# RAMBo.net
KiCad netlist of a schematic drawn in EAGLE
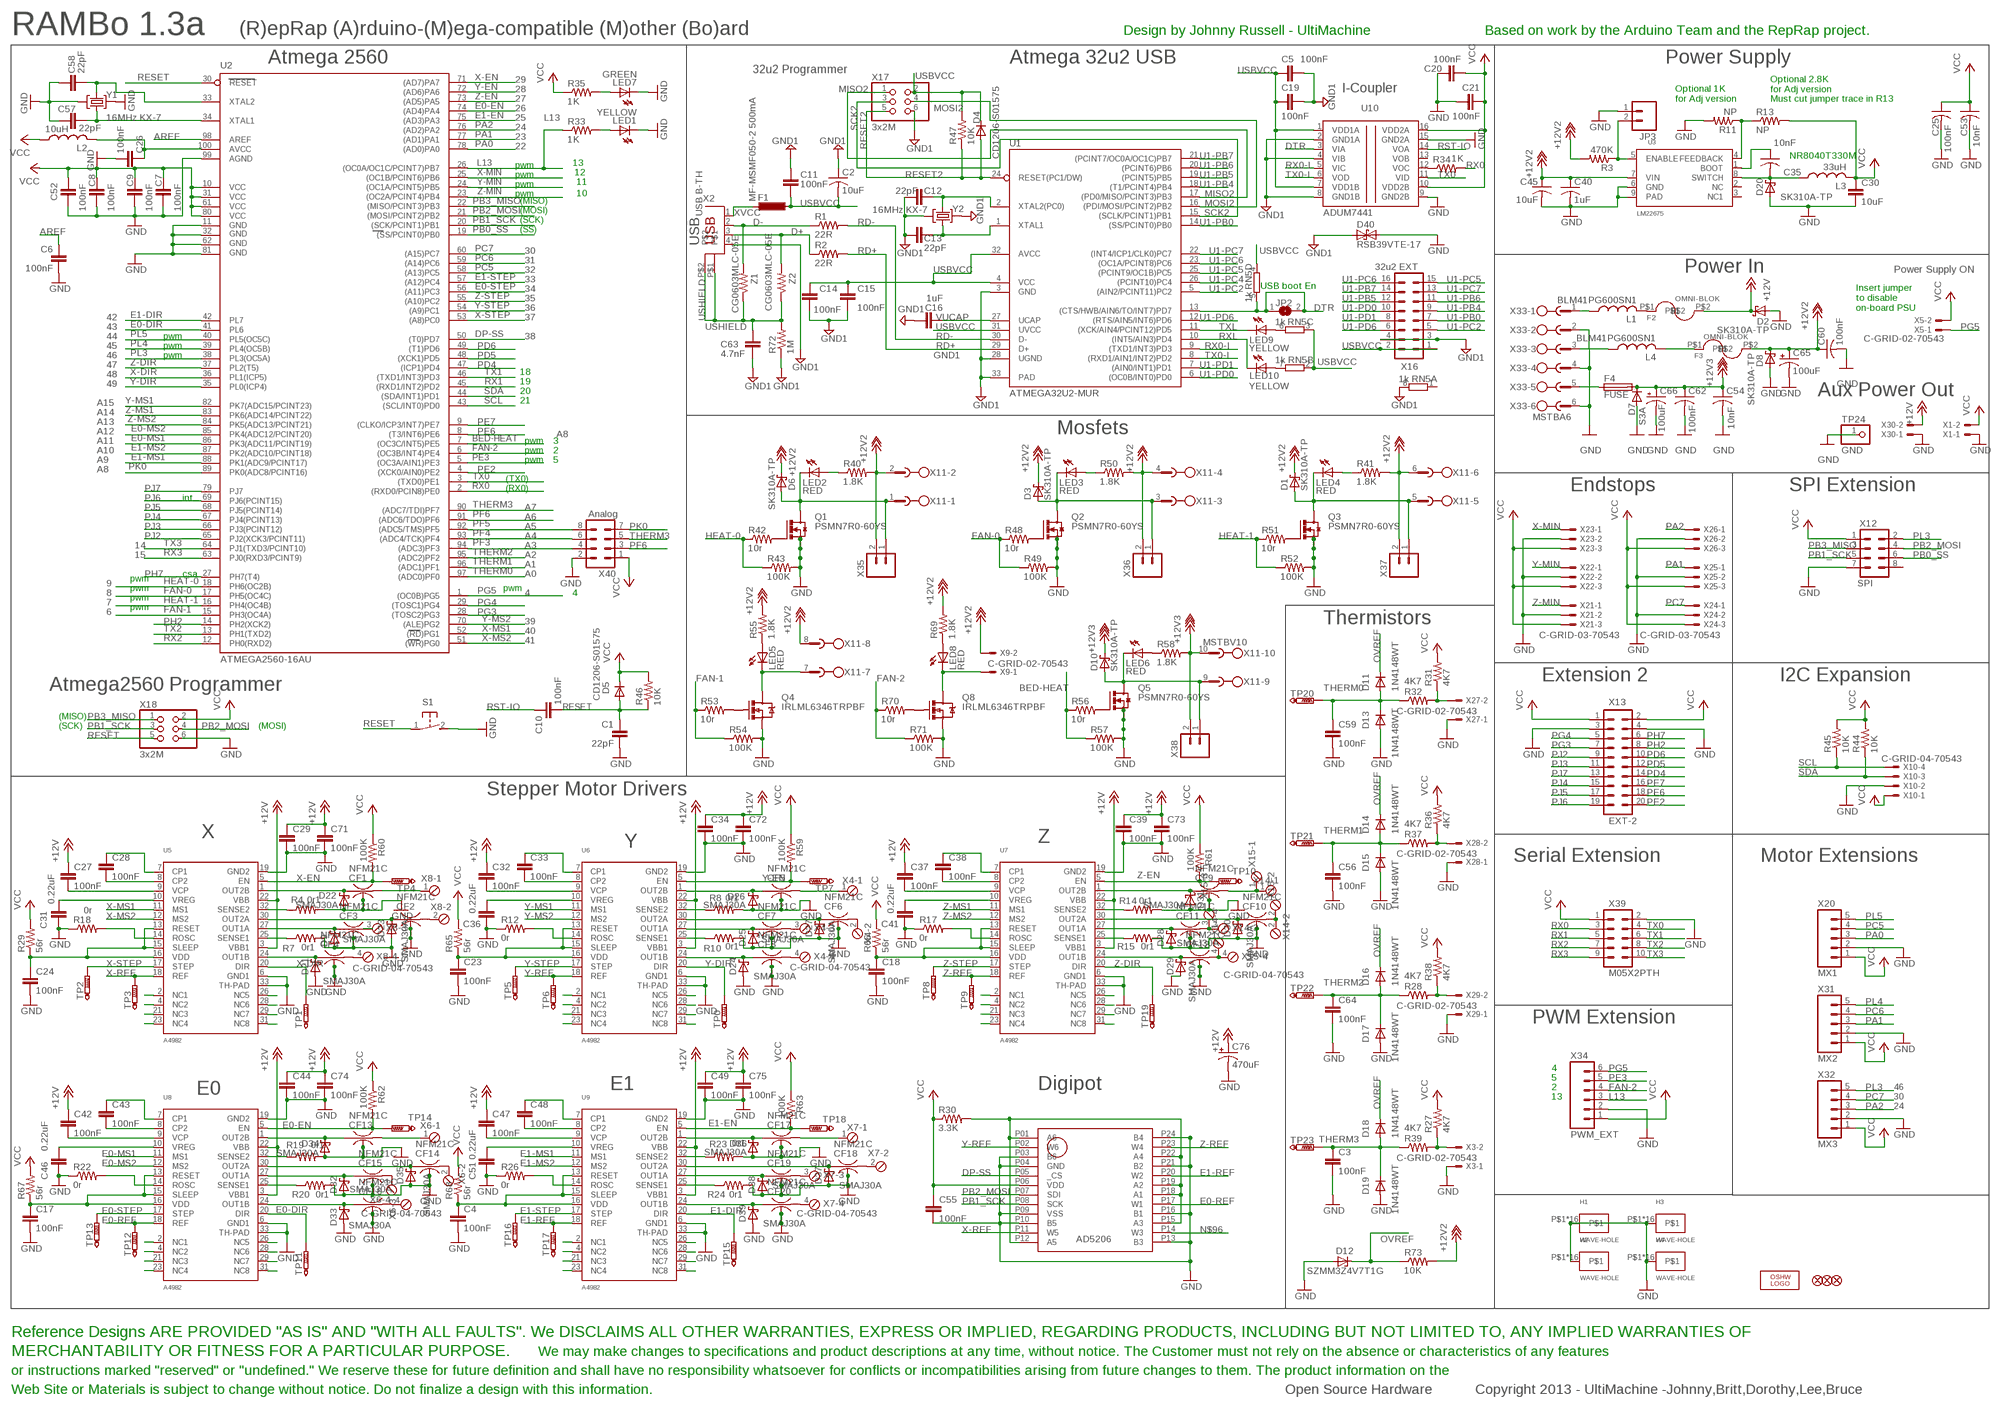
[diagram p0: schematic, sheet 1]

(export (version "E")
  (design (tool "Eeschema 10.0.6"))
  (components
    (comp (ref "C1")
      (value "22pF")
      (footprint "eagle-import:C0603")
      (libsource (lib "eagle-import") (part "resistor_C-EUC0603"))
    )
    (comp (ref "C2")
      (value "10uF")
      (footprint "eagle-import:C0805")
      (libsource (lib "eagle-import") (part "C-USC0805"))
    )
    (comp (ref "C3")
      (value "100nF")
      (footprint "eagle-import:C0603")
      (libsource (lib "eagle-import") (part "resistor_C-EUC0603"))
    )
    (comp (ref "C4")
      (value "100nF")
      (footprint "eagle-import:C0603")
      (libsource (lib "eagle-import") (part "resistor_C-EUC0603"))
    )
    (comp (ref "C5")
      (value "100nF")
      (footprint "eagle-import:C0402")
      (libsource (lib "eagle-import") (part "C-EUC0402"))
    )
    (comp (ref "C6")
      (value "100nF")
      (footprint "eagle-import:C0603")
      (libsource (lib "eagle-import") (part "resistor_C-EUC0603"))
    )
    (comp (ref "C7")
      (value "100nF")
      (footprint "eagle-import:C0603")
      (libsource (lib "eagle-import") (part "resistor_C-EUC0603"))
    )
    (comp (ref "C8")
      (value "100nF")
      (footprint "eagle-import:C0603")
      (libsource (lib "eagle-import") (part "resistor_C-EUC0603"))
    )
    (comp (ref "C9")
      (value "100nF")
      (footprint "eagle-import:C0603")
      (libsource (lib "eagle-import") (part "resistor_C-EUC0603"))
    )
    (comp (ref "C10")
      (value "100nF")
      (footprint "eagle-import:C0603")
      (libsource (lib "eagle-import") (part "resistor_C-EUC0603"))
    )
    (comp (ref "C11")
      (value "100nF")
      (footprint "eagle-import:C0603")
      (libsource (lib "eagle-import") (part "resistor_C-EUC0603"))
    )
    (comp (ref "C12")
      (value "22pF")
      (footprint "eagle-import:C0603")
      (libsource (lib "eagle-import") (part "resistor_C-EUC0603"))
    )
    (comp (ref "C13")
      (value "22pF")
      (footprint "eagle-import:C0603")
      (libsource (lib "eagle-import") (part "resistor_C-EUC0603"))
    )
    (comp (ref "C14")
      (value "100nF")
      (footprint "eagle-import:C0603")
      (libsource (lib "eagle-import") (part "resistor_C-EUC0603"))
    )
    (comp (ref "C15")
      (value "100nF")
      (footprint "eagle-import:C0603")
      (libsource (lib "eagle-import") (part "resistor_C-EUC0603"))
    )
    (comp (ref "C16")
      (value "1uF")
      (footprint "eagle-import:C0603")
      (libsource (lib "eagle-import") (part "resistor_C-EUC0603"))
    )
    (comp (ref "C17")
      (value "100nF")
      (footprint "eagle-import:C0603")
      (libsource (lib "eagle-import") (part "resistor_C-EUC0603"))
    )
    (comp (ref "C18")
      (value "100nF")
      (footprint "eagle-import:C0603")
      (libsource (lib "eagle-import") (part "resistor_C-EUC0603"))
    )
    (comp (ref "C19")
      (value "100nF")
      (footprint "eagle-import:C0402")
      (libsource (lib "eagle-import") (part "C-EUC0402"))
    )
    (comp (ref "C20")
      (value "100nF")
      (footprint "eagle-import:C0402")
      (libsource (lib "eagle-import") (part "C-EUC0402"))
    )
    (comp (ref "C21")
      (value "100nF")
      (footprint "eagle-import:C0402")
      (libsource (lib "eagle-import") (part "C-EUC0402"))
    )
    (comp (ref "C23")
      (value "100nF")
      (footprint "eagle-import:C0603")
      (libsource (lib "eagle-import") (part "resistor_C-EUC0603"))
    )
    (comp (ref "C24")
      (value "100nF")
      (footprint "eagle-import:C0603")
      (libsource (lib "eagle-import") (part "resistor_C-EUC0603"))
    )
    (comp (ref "C25")
      (value "100nF")
      (footprint "eagle-import:C0603")
      (libsource (lib "eagle-import") (part "C-USC0603"))
    )
    (comp (ref "C26")
      (value "100nF")
      (footprint "eagle-import:C0603")
      (libsource (lib "eagle-import") (part "resistor_C-EUC0603"))
    )
    (comp (ref "C27")
      (value "100nF")
      (footprint "eagle-import:C0603")
      (libsource (lib "eagle-import") (part "resistor_C-EUC0603"))
    )
    (comp (ref "C28")
      (value "100nF")
      (footprint "eagle-import:C0603")
      (libsource (lib "eagle-import") (part "resistor_C-EUC0603"))
    )
    (comp (ref "C29")
      (value "100nF")
      (footprint "eagle-import:C0603")
      (libsource (lib "eagle-import") (part "resistor_C-EUC0603"))
    )
    (comp (ref "C30")
      (value "10uF")
      (footprint "eagle-import:C1210K")
      (libsource (lib "eagle-import") (part "resistor_C-EUC1210K"))
    )
    (comp (ref "C31")
      (value "0.22uF")
      (footprint "eagle-import:C0603")
      (libsource (lib "eagle-import") (part "resistor_C-EUC0603"))
    )
    (comp (ref "C32")
      (value "100nF")
      (footprint "eagle-import:C0603")
      (libsource (lib "eagle-import") (part "resistor_C-EUC0603"))
    )
    (comp (ref "C33")
      (value "100nF")
      (footprint "eagle-import:C0603")
      (libsource (lib "eagle-import") (part "resistor_C-EUC0603"))
    )
    (comp (ref "C34")
      (value "100nF")
      (footprint "eagle-import:C0603")
      (libsource (lib "eagle-import") (part "resistor_C-EUC0603"))
    )
    (comp (ref "C35")
      (value "10nF")
      (footprint "eagle-import:C0603")
      (libsource (lib "eagle-import") (part "C-USC0603"))
    )
    (comp (ref "C36")
      (value "0.22uF")
      (footprint "eagle-import:C0603")
      (libsource (lib "eagle-import") (part "resistor_C-EUC0603"))
    )
    (comp (ref "C37")
      (value "100nF")
      (footprint "eagle-import:C0603")
      (libsource (lib "eagle-import") (part "resistor_C-EUC0603"))
    )
    (comp (ref "C38")
      (value "100nF")
      (footprint "eagle-import:C0603")
      (libsource (lib "eagle-import") (part "resistor_C-EUC0603"))
    )
    (comp (ref "C39")
      (value "100nF")
      (footprint "eagle-import:C0603")
      (libsource (lib "eagle-import") (part "resistor_C-EUC0603"))
    )
    (comp (ref "C40")
      (value "1uF")
      (footprint "eagle-import:C0805")
      (libsource (lib "eagle-import") (part "C-USC0805"))
    )
    (comp (ref "C41")
      (value "0.22uF")
      (footprint "eagle-import:C0603")
      (libsource (lib "eagle-import") (part "resistor_C-EUC0603"))
    )
    (comp (ref "C42")
      (value "100nF")
      (footprint "eagle-import:C0603")
      (libsource (lib "eagle-import") (part "resistor_C-EUC0603"))
    )
    (comp (ref "C43")
      (value "100nF")
      (footprint "eagle-import:C0603")
      (libsource (lib "eagle-import") (part "resistor_C-EUC0603"))
    )
    (comp (ref "C44")
      (value "100nF")
      (footprint "eagle-import:C0603")
      (libsource (lib "eagle-import") (part "resistor_C-EUC0603"))
    )
    (comp (ref "C45")
      (value "10uF")
      (footprint "eagle-import:C2220K")
      (libsource (lib "eagle-import") (part "C-USC2220K"))
    )
    (comp (ref "C46")
      (value "0.22uF")
      (footprint "eagle-import:C0603")
      (libsource (lib "eagle-import") (part "resistor_C-EUC0603"))
    )
    (comp (ref "C47")
      (value "100nF")
      (footprint "eagle-import:C0603")
      (libsource (lib "eagle-import") (part "resistor_C-EUC0603"))
    )
    (comp (ref "C48")
      (value "100nF")
      (footprint "eagle-import:C0603")
      (libsource (lib "eagle-import") (part "resistor_C-EUC0603"))
    )
    (comp (ref "C49")
      (value "100nF")
      (footprint "eagle-import:C0603")
      (libsource (lib "eagle-import") (part "resistor_C-EUC0603"))
    )
    (comp (ref "C51")
      (value "0.22uF")
      (footprint "eagle-import:C0603")
      (libsource (lib "eagle-import") (part "resistor_C-EUC0603"))
    )
    (comp (ref "C52")
      (value "100nF")
      (footprint "eagle-import:C0603")
      (libsource (lib "eagle-import") (part "resistor_C-EUC0603"))
    )
    (comp (ref "C53")
      (value "10nF")
      (footprint "eagle-import:C0603")
      (libsource (lib "eagle-import") (part "C-USC0603"))
    )
    (comp (ref "C54")
      (value "10nF")
      (footprint "eagle-import:C0603")
      (libsource (lib "eagle-import") (part "C-USC0603"))
    )
    (comp (ref "C55")
      (value "100nF")
      (footprint "eagle-import:C0603")
      (libsource (lib "eagle-import") (part "resistor_C-EUC0603"))
    )
    (comp (ref "C56")
      (value "100nF")
      (footprint "eagle-import:C0603")
      (libsource (lib "eagle-import") (part "resistor_C-EUC0603"))
    )
    (comp (ref "C57")
      (value "22pF")
      (footprint "eagle-import:C0603")
      (libsource (lib "eagle-import") (part "resistor_C-EUC0603"))
    )
    (comp (ref "C58")
      (value "22pF")
      (footprint "eagle-import:C0603")
      (libsource (lib "eagle-import") (part "resistor_C-EUC0603"))
    )
    (comp (ref "C59")
      (value "100nF")
      (footprint "eagle-import:C0603")
      (libsource (lib "eagle-import") (part "resistor_C-EUC0603"))
    )
    (comp (ref "C60")
      (value "100nF")
      (footprint "eagle-import:C0603")
      (libsource (lib "eagle-import") (part "C-USC0603"))
    )
    (comp (ref "C62")
      (value "100nF")
      (footprint "eagle-import:C0603")
      (libsource (lib "eagle-import") (part "C-USC0603"))
    )
    (comp (ref "C63")
      (value "4.7nF")
      (footprint "eagle-import:C0402")
      (libsource (lib "eagle-import") (part "C-EUC0402"))
    )
    (comp (ref "C64")
      (value "100nF")
      (footprint "eagle-import:C0603")
      (libsource (lib "eagle-import") (part "resistor_C-EUC0603"))
    )
    (comp (ref "C65")
      (value "100uF")
      (footprint "eagle-import:E3,5-8")
      (libsource (lib "eagle-import") (part "CPOL-USE3.5-8"))
    )
    (comp (ref "C66")
      (value "100uF")
      (footprint "eagle-import:E3,5-8")
      (libsource (lib "eagle-import") (part "CPOL-USE3.5-8"))
    )
    (comp (ref "C71")
      (value "100nF")
      (footprint "eagle-import:C0603")
      (libsource (lib "eagle-import") (part "resistor_C-EUC0603"))
    )
    (comp (ref "C72")
      (value "100nF")
      (footprint "eagle-import:C0603")
      (libsource (lib "eagle-import") (part "resistor_C-EUC0603"))
    )
    (comp (ref "C73")
      (value "100nF")
      (footprint "eagle-import:C0603")
      (libsource (lib "eagle-import") (part "resistor_C-EUC0603"))
    )
    (comp (ref "C74")
      (value "100nF")
      (footprint "eagle-import:C0603")
      (libsource (lib "eagle-import") (part "resistor_C-EUC0603"))
    )
    (comp (ref "C75")
      (value "100nF")
      (footprint "eagle-import:C0603")
      (libsource (lib "eagle-import") (part "resistor_C-EUC0603"))
    )
    (comp (ref "C76")
      (value "470uF")
      (footprint "eagle-import:C12,5-5")
      (libsource (lib "eagle-import") (part "CPOL-USC12,5-5"))
    )
    (comp (ref "CF1")
      (value "NFM21C")
      (footprint "eagle-import:NFM21C")
      (fields (field (name "MPN") "NFM21CC102R1H3D"))
      (libsource (lib "eagle-import") (part "NFM21C"))
    )
    (comp (ref "CF2")
      (value "NFM21C")
      (footprint "eagle-import:NFM21C")
      (fields (field (name "MPN") "NFM21CC102R1H3D"))
      (libsource (lib "eagle-import") (part "NFM21C"))
    )
    (comp (ref "CF3")
      (value "NFM21C")
      (footprint "eagle-import:NFM21C")
      (fields (field (name "MPN") "NFM21CC102R1H3D"))
      (libsource (lib "eagle-import") (part "NFM21C"))
    )
    (comp (ref "CF4")
      (value "NFM21C")
      (footprint "eagle-import:NFM21C")
      (fields (field (name "MPN") "NFM21CC102R1H3D"))
      (libsource (lib "eagle-import") (part "NFM21C"))
    )
    (comp (ref "CF5")
      (value "NFM21C")
      (footprint "eagle-import:NFM21C")
      (fields (field (name "MPN") "NFM21CC102R1H3D"))
      (libsource (lib "eagle-import") (part "NFM21C"))
    )
    (comp (ref "CF6")
      (value "NFM21C")
      (footprint "eagle-import:NFM21C")
      (fields (field (name "MPN") "NFM21CC102R1H3D"))
      (libsource (lib "eagle-import") (part "NFM21C"))
    )
    (comp (ref "CF7")
      (value "NFM21C")
      (footprint "eagle-import:NFM21C")
      (fields (field (name "MPN") "NFM21CC102R1H3D"))
      (libsource (lib "eagle-import") (part "NFM21C"))
    )
    (comp (ref "CF8")
      (value "NFM21C")
      (footprint "eagle-import:NFM21C")
      (fields (field (name "MPN") "NFM21CC102R1H3D"))
      (libsource (lib "eagle-import") (part "NFM21C"))
    )
    (comp (ref "CF9")
      (value "NFM21C")
      (footprint "eagle-import:NFM21C")
      (fields (field (name "MPN") "NFM21CC102R1H3D"))
      (libsource (lib "eagle-import") (part "NFM21C"))
    )
    (comp (ref "CF10")
      (value "NFM21C")
      (footprint "eagle-import:NFM21C")
      (fields (field (name "MPN") "NFM21CC102R1H3D"))
      (libsource (lib "eagle-import") (part "NFM21C"))
    )
    (comp (ref "CF11")
      (value "NFM21C")
      (footprint "eagle-import:NFM21C")
      (fields (field (name "MPN") "NFM21CC102R1H3D"))
      (libsource (lib "eagle-import") (part "NFM21C"))
    )
    (comp (ref "CF12")
      (value "NFM21C")
      (footprint "eagle-import:NFM21C")
      (fields (field (name "MPN") "NFM21CC102R1H3D"))
      (libsource (lib "eagle-import") (part "NFM21C"))
    )
    (comp (ref "CF13")
      (value "NFM21C")
      (footprint "eagle-import:NFM21C")
      (fields (field (name "MPN") "NFM21CC102R1H3D"))
      (libsource (lib "eagle-import") (part "NFM21C"))
    )
    (comp (ref "CF14")
      (value "NFM21C")
      (footprint "eagle-import:NFM21C")
      (fields (field (name "MPN") "NFM21CC102R1H3D"))
      (libsource (lib "eagle-import") (part "NFM21C"))
    )
    (comp (ref "CF15")
      (value "NFM21C")
      (footprint "eagle-import:NFM21C")
      (fields (field (name "MPN") "NFM21CC102R1H3D"))
      (libsource (lib "eagle-import") (part "NFM21C"))
    )
    (comp (ref "CF16")
      (value "NFM21C")
      (footprint "eagle-import:NFM21C")
      (fields (field (name "MPN") "NFM21CC102R1H3D"))
      (libsource (lib "eagle-import") (part "NFM21C"))
    )
    (comp (ref "CF17")
      (value "NFM21C")
      (footprint "eagle-import:NFM21C")
      (fields (field (name "MPN") "NFM21CC102R1H3D"))
      (libsource (lib "eagle-import") (part "NFM21C"))
    )
    (comp (ref "CF18")
      (value "NFM21C")
      (footprint "eagle-import:NFM21C")
      (fields (field (name "MPN") "NFM21CC102R1H3D"))
      (libsource (lib "eagle-import") (part "NFM21C"))
    )
    (comp (ref "CF19")
      (value "NFM21C")
      (footprint "eagle-import:NFM21C")
      (fields (field (name "MPN") "NFM21CC102R1H3D"))
      (libsource (lib "eagle-import") (part "NFM21C"))
    )
    (comp (ref "CF20")
      (value "NFM21C")
      (footprint "eagle-import:NFM21C")
      (fields (field (name "MPN") "NFM21CC102R1H3D"))
      (libsource (lib "eagle-import") (part "NFM21C"))
    )
    (comp (ref "D1")
      (value "SK310A-TP")
      (footprint "eagle-import:SMA-SM")
      (libsource (lib "eagle-import") (part "SCHOTTKY-DIODE"))
    )
    (comp (ref "D2")
      (value "SK310A-TP")
      (footprint "eagle-import:SMA-SM")
      (libsource (lib "eagle-import") (part "SCHOTTKY-DIODE"))
    )
    (comp (ref "D3")
      (value "SK310A-TP")
      (footprint "eagle-import:SMA-SM")
      (libsource (lib "eagle-import") (part "SCHOTTKY-DIODE"))
    )
    (comp (ref "D4")
      (value "CD1206-S01575")
      (footprint "eagle-import:MINIMELF")
      (libsource (lib "eagle-import") (part "DIODE-MINIMELF"))
    )
    (comp (ref "D5")
      (value "CD1206-S01575")
      (footprint "eagle-import:MINIMELF")
      (libsource (lib "eagle-import") (part "DIODE-MINIMELF"))
    )
    (comp (ref "D6")
      (value "SK310A-TP")
      (footprint "eagle-import:SMA-SM")
      (libsource (lib "eagle-import") (part "SCHOTTKY-DIODE"))
    )
    (comp (ref "D7")
      (value "S3A")
      (footprint "eagle-import:DO-214AB")
      (libsource (lib "eagle-import") (part "DIODE-D0-214AB"))
    )
    (comp (ref "D8")
      (value "SK310A-TP")
      (footprint "eagle-import:SMA-SM")
      (libsource (lib "eagle-import") (part "SCHOTTKY-DIODE"))
    )
    (comp (ref "D9")
      (value "SMAJ30A")
      (footprint "eagle-import:SMA-SM")
      (libsource (lib "eagle-import") (part "SCHOTTKY-DIODE"))
    )
    (comp (ref "D10")
      (value "SK310A-TP")
      (footprint "eagle-import:SMA-SM")
      (libsource (lib "eagle-import") (part "SCHOTTKY-DIODE"))
    )
    (comp (ref "D11")
      (value "1N4148WT")
      (footprint "eagle-import:SOD523")
      (libsource (lib "eagle-import") (part "1N4148WT"))
    )
    (comp (ref "D12")
      (value "SZMM3Z4V7T1G")
      (footprint "eagle-import:SOD323-R")
      (libsource (lib "eagle-import") (part "ZENER-DIODESOD323"))
    )
    (comp (ref "D13")
      (value "1N4148WT")
      (footprint "eagle-import:SOD523")
      (libsource (lib "eagle-import") (part "1N4148WT"))
    )
    (comp (ref "D14")
      (value "1N4148WT")
      (footprint "eagle-import:SOD523")
      (libsource (lib "eagle-import") (part "1N4148WT"))
    )
    (comp (ref "D15")
      (value "1N4148WT")
      (footprint "eagle-import:SOD523")
      (libsource (lib "eagle-import") (part "1N4148WT"))
    )
    (comp (ref "D16")
      (value "1N4148WT")
      (footprint "eagle-import:SOD523")
      (libsource (lib "eagle-import") (part "1N4148WT"))
    )
    (comp (ref "D17")
      (value "1N4148WT")
      (footprint "eagle-import:SOD523")
      (libsource (lib "eagle-import") (part "1N4148WT"))
    )
    (comp (ref "D18")
      (value "1N4148WT")
      (footprint "eagle-import:SOD523")
      (libsource (lib "eagle-import") (part "1N4148WT"))
    )
    (comp (ref "D19")
      (value "1N4148WT")
      (footprint "eagle-import:SOD523")
      (libsource (lib "eagle-import") (part "1N4148WT"))
    )
    (comp (ref "D20")
      (value "SK310A-TP")
      (footprint "eagle-import:SMA-SM")
      (libsource (lib "eagle-import") (part "SCHOTTKY-DIODE"))
    )
    (comp (ref "D21")
      (value "SMAJ30A")
      (footprint "eagle-import:SMA-SM")
      (libsource (lib "eagle-import") (part "SCHOTTKY-DIODE"))
    )
    (comp (ref "D22")
      (value "SMAJ30A")
      (footprint "eagle-import:SMA-SM")
      (libsource (lib "eagle-import") (part "SCHOTTKY-DIODE"))
    )
    (comp (ref "D23")
      (value "SMAJ30A")
      (footprint "eagle-import:SMA-SM")
      (libsource (lib "eagle-import") (part "SCHOTTKY-DIODE"))
    )
    (comp (ref "D24")
      (value "SMAJ30A")
      (footprint "eagle-import:SMA-SM")
      (libsource (lib "eagle-import") (part "SCHOTTKY-DIODE"))
    )
    (comp (ref "D25")
      (value "SMAJ30A")
      (footprint "eagle-import:SMA-SM")
      (libsource (lib "eagle-import") (part "SCHOTTKY-DIODE"))
    )
    (comp (ref "D26")
      (value "SMAJ30A")
      (footprint "eagle-import:SMA-SM")
      (libsource (lib "eagle-import") (part "SCHOTTKY-DIODE"))
    )
    (comp (ref "D27")
      (value "SMAJ30A")
      (footprint "eagle-import:SMA-SM")
      (libsource (lib "eagle-import") (part "SCHOTTKY-DIODE"))
    )
    (comp (ref "D28")
      (value "SMAJ30A")
      (footprint "eagle-import:SMA-SM")
      (libsource (lib "eagle-import") (part "SCHOTTKY-DIODE"))
    )
    (comp (ref "D29")
      (value "SMAJ30A")
      (footprint "eagle-import:SMA-SM")
      (libsource (lib "eagle-import") (part "SCHOTTKY-DIODE"))
    )
    (comp (ref "D30")
      (value "SMAJ30A")
      (footprint "eagle-import:SMA-SM")
      (libsource (lib "eagle-import") (part "SCHOTTKY-DIODE"))
    )
    (comp (ref "D31")
      (value "SMAJ30A")
      (footprint "eagle-import:SMA-SM")
      (libsource (lib "eagle-import") (part "SCHOTTKY-DIODE"))
    )
    (comp (ref "D32")
      (value "SMAJ30A")
      (footprint "eagle-import:SMA-SM")
      (libsource (lib "eagle-import") (part "SCHOTTKY-DIODE"))
    )
    (comp (ref "D33")
      (value "SMAJ30A")
      (footprint "eagle-import:SMA-SM")
      (libsource (lib "eagle-import") (part "SCHOTTKY-DIODE"))
    )
    (comp (ref "D34")
      (value "SMAJ30A")
      (footprint "eagle-import:SMA-SM")
      (libsource (lib "eagle-import") (part "SCHOTTKY-DIODE"))
    )
    (comp (ref "D35")
      (value "SMAJ30A")
      (footprint "eagle-import:SMA-SM")
      (libsource (lib "eagle-import") (part "SCHOTTKY-DIODE"))
    )
    (comp (ref "D36")
      (value "SMAJ30A")
      (footprint "eagle-import:SMA-SM")
      (libsource (lib "eagle-import") (part "SCHOTTKY-DIODE"))
    )
    (comp (ref "D37")
      (value "SMAJ30A")
      (footprint "eagle-import:SMA-SM")
      (libsource (lib "eagle-import") (part "SCHOTTKY-DIODE"))
    )
    (comp (ref "D38")
      (value "SMAJ30A")
      (footprint "eagle-import:SMA-SM")
      (libsource (lib "eagle-import") (part "SCHOTTKY-DIODE"))
    )
    (comp (ref "D39")
      (value "SMAJ30A")
      (footprint "eagle-import:SMA-SM")
      (libsource (lib "eagle-import") (part "SCHOTTKY-DIODE"))
    )
    (comp (ref "D40")
      (value "RSB39VTE-17")
      (footprint "eagle-import:SOD323-R")
      (libsource (lib "eagle-import") (part "TVS-BISOD323"))
    )
    (comp (ref "F1")
      (value "MF-MSMF050-2 500mA")
      (footprint "eagle-import:L1812")
      (libsource (lib "eagle-import") (part "L-EUL1812"))
    )
    (comp (ref "F2")
      (value "OMNI-BLOK")
      (footprint "eagle-import:OMNI-BLOK")
      (libsource (lib "eagle-import") (part "OMNI-BLOK"))
    )
    (comp (ref "F3")
      (value "OMNI-BLOK")
      (footprint "eagle-import:OMNI-BLOK")
      (libsource (lib "eagle-import") (part "OMNI-BLOK"))
    )
    (comp (ref "F4")
      (value "FUSE")
      (footprint "eagle-import:FUSE-ATO-SMD")
      (libsource (lib "eagle-import") (part "FUSE"))
    )
    (comp (ref "FID1")
      (value "FIDUCIAL1X2.5")
      (footprint "eagle-import:FIDUCIAL-1X2.5")
      (libsource (lib "eagle-import") (part "FIDUCIAL1X2.5"))
    )
    (comp (ref "FID2")
      (value "FIDUCIAL1X2.5")
      (footprint "eagle-import:FIDUCIAL-1X2.5")
      (libsource (lib "eagle-import") (part "FIDUCIAL1X2.5"))
    )
    (comp (ref "FID3")
      (value "FIDUCIAL1X2.5")
      (footprint "eagle-import:FIDUCIAL-1X2.5")
      (libsource (lib "eagle-import") (part "FIDUCIAL1X2.5"))
    )
    (comp (ref "H1")
      (value "WAVE-HOLE")
      (footprint "eagle-import:3,0-WAVE-HOLE")
      (libsource (lib "eagle-import") (part "WAVE-HOLE"))
    )
    (comp (ref "H2")
      (value "WAVE-HOLE")
      (footprint "eagle-import:3,0-WAVE-HOLE")
      (libsource (lib "eagle-import") (part "WAVE-HOLE"))
    )
    (comp (ref "H3")
      (value "WAVE-HOLE")
      (footprint "eagle-import:3,0-WAVE-HOLE")
      (libsource (lib "eagle-import") (part "WAVE-HOLE"))
    )
    (comp (ref "H4")
      (value "WAVE-HOLE")
      (footprint "eagle-import:3,0-WAVE-HOLE")
      (libsource (lib "eagle-import") (part "WAVE-HOLE"))
    )
    (comp (ref "JP2") (value "SJ") (footprint "eagle-import:SJ") (libsource (lib "eagle-import") (part "SJ")))
    (comp (ref "JP3")
      (value "M02PTH")
      (footprint "eagle-import:1X02")
      (libsource (lib "eagle-import") (part "M02PTH"))
    )
    (comp (ref "L1")
      (value "BLM41PG600SN1")
      (footprint "eagle-import:L1806")
      (libsource (lib "eagle-import") (part "L-USL1806"))
    )
    (comp (ref "L2")
      (value "10uH")
      (footprint "eagle-import:C0805")
      (libsource (lib "eagle-import") (part "L-US"))
    )
    (comp (ref "L3")
      (value "33uH")
      (footprint "eagle-import:NR8040")
      (libsource (lib "eagle-import") (part "L-USNR8040"))
    )
    (comp (ref "L4")
      (value "BLM41PG600SN1")
      (footprint "eagle-import:L1806")
      (libsource (lib "eagle-import") (part "L-USL1806"))
    )
    (comp (ref "LED1")
      (value "YELLOW")
      (footprint "eagle-import:CHIP-LED0805")
      (libsource (lib "eagle-import") (part "LEDCHIP-LED0805"))
    )
    (comp (ref "LED2")
      (value "RED")
      (footprint "eagle-import:CHIP-LED0805")
      (libsource (lib "eagle-import") (part "LEDCHIP-LED0805"))
    )
    (comp (ref "LED3")
      (value "RED")
      (footprint "eagle-import:CHIP-LED0805")
      (libsource (lib "eagle-import") (part "LEDCHIP-LED0805"))
    )
    (comp (ref "LED4")
      (value "RED")
      (footprint "eagle-import:CHIP-LED0805")
      (libsource (lib "eagle-import") (part "LEDCHIP-LED0805"))
    )
    (comp (ref "LED5")
      (value "RED")
      (footprint "eagle-import:CHIP-LED0805")
      (libsource (lib "eagle-import") (part "LEDCHIP-LED0805"))
    )
    (comp (ref "LED6")
      (value "RED")
      (footprint "eagle-import:CHIP-LED0805")
      (libsource (lib "eagle-import") (part "LEDCHIP-LED0805"))
    )
    (comp (ref "LED7")
      (value "GREEN")
      (footprint "eagle-import:CHIP-LED0805")
      (libsource (lib "eagle-import") (part "LEDCHIP-LED0805"))
    )
    (comp (ref "LED8")
      (value "RED")
      (footprint "eagle-import:CHIP-LED0805")
      (libsource (lib "eagle-import") (part "LEDCHIP-LED0805"))
    )
    (comp (ref "LED9")
      (value "YELLOW")
      (footprint "eagle-import:CHIP-LED0805")
      (libsource (lib "eagle-import") (part "LEDCHIP-LED0805"))
    )
    (comp (ref "LED10")
      (value "YELLOW")
      (footprint "eagle-import:CHIP-LED0805")
      (libsource (lib "eagle-import") (part "LEDCHIP-LED0805"))
    )
    (comp (ref "LOGO1")
      (value "OSHW_LOGO_8MILX0150-NT")
      (footprint "eagle-import:OSHW_8X150_NOTEXT")
      (libsource (lib "eagle-import") (part "OSHW_LOGO_8MILX0150-NT"))
    )
    (comp (ref "Q1")
      (value "PSMN7R0-60YS")
      (footprint "eagle-import:SOT669")
      (libsource (lib "eagle-import") (part "PH7030L"))
    )
    (comp (ref "Q2")
      (value "PSMN7R0-60YS")
      (footprint "eagle-import:SOT669")
      (libsource (lib "eagle-import") (part "PH7030L"))
    )
    (comp (ref "Q3")
      (value "PSMN7R0-60YS")
      (footprint "eagle-import:SOT669")
      (libsource (lib "eagle-import") (part "PH7030L"))
    )
    (comp (ref "Q4")
      (value "IRLML6346TRPBF")
      (footprint "eagle-import:SOT23-3")
      (libsource (lib "eagle-import") (part "MOSFET-NCHANNELSMD"))
    )
    (comp (ref "Q5")
      (value "PSMN7R0-60YS")
      (footprint "eagle-import:SOT669")
      (libsource (lib "eagle-import") (part "PH7030L"))
    )
    (comp (ref "Q8")
      (value "IRLML6346TRPBF")
      (footprint "eagle-import:SOT23-3")
      (libsource (lib "eagle-import") (part "MOSFET-NCHANNELSMD"))
    )
    (comp (ref "R1")
      (value "22R")
      (footprint "eagle-import:R0402")
      (libsource (lib "eagle-import") (part "R-US_R0402"))
    )
    (comp (ref "R2")
      (value "22R")
      (footprint "eagle-import:R0402")
      (libsource (lib "eagle-import") (part "R-US_R0402"))
    )
    (comp (ref "R3")
      (value "470K")
      (footprint "eagle-import:R0603")
      (libsource (lib "eagle-import") (part "resistor_R-US_R0603"))
    )
    (comp (ref "R4")
      (value "0r1")
      (footprint "eagle-import:R1206")
      (libsource (lib "eagle-import") (part "resistor_R-US_R1206"))
    )
    (comp (ref "R7")
      (value "0r1")
      (footprint "eagle-import:R1206")
      (libsource (lib "eagle-import") (part "resistor_R-US_R1206"))
    )
    (comp (ref "R8")
      (value "0r1")
      (footprint "eagle-import:R1206")
      (libsource (lib "eagle-import") (part "resistor_R-US_R1206"))
    )
    (comp (ref "R10")
      (value "0r1")
      (footprint "eagle-import:R1206")
      (libsource (lib "eagle-import") (part "resistor_R-US_R1206"))
    )
    (comp (ref "R11")
      (value "NP")
      (footprint "eagle-import:R0603")
      (libsource (lib "eagle-import") (part "resistor_R-US_R0603"))
    )
    (comp (ref "R12")
      (value "0r")
      (footprint "eagle-import:R0603")
      (libsource (lib "eagle-import") (part "resistor_R-US_R0603"))
    )
    (comp (ref "R13")
      (value "NP")
      (footprint "eagle-import:R0603")
      (libsource (lib "eagle-import") (part "resistor_R-US_R0603"))
    )
    (comp (ref "R14")
      (value "0r1")
      (footprint "eagle-import:R1206")
      (libsource (lib "eagle-import") (part "resistor_R-US_R1206"))
    )
    (comp (ref "R15")
      (value "0r1")
      (footprint "eagle-import:R1206")
      (libsource (lib "eagle-import") (part "resistor_R-US_R1206"))
    )
    (comp (ref "R17")
      (value "0r")
      (footprint "eagle-import:R0603")
      (libsource (lib "eagle-import") (part "resistor_R-US_R0603"))
    )
    (comp (ref "R18")
      (value "0r")
      (footprint "eagle-import:R0603")
      (libsource (lib "eagle-import") (part "resistor_R-US_R0603"))
    )
    (comp (ref "R19")
      (value "0r1")
      (footprint "eagle-import:R1206")
      (libsource (lib "eagle-import") (part "resistor_R-US_R1206"))
    )
    (comp (ref "R20")
      (value "0r1")
      (footprint "eagle-import:R1206")
      (libsource (lib "eagle-import") (part "resistor_R-US_R1206"))
    )
    (comp (ref "R22")
      (value "0r")
      (footprint "eagle-import:R0603")
      (libsource (lib "eagle-import") (part "resistor_R-US_R0603"))
    )
    (comp (ref "R23")
      (value "0r1")
      (footprint "eagle-import:R1206")
      (libsource (lib "eagle-import") (part "resistor_R-US_R1206"))
    )
    (comp (ref "R24")
      (value "0r1")
      (footprint "eagle-import:R1206")
      (libsource (lib "eagle-import") (part "resistor_R-US_R1206"))
    )
    (comp (ref "R26")
      (value "0r")
      (footprint "eagle-import:R0603")
      (libsource (lib "eagle-import") (part "resistor_R-US_R0603"))
    )
    (comp (ref "R27")
      (value "4K7")
      (footprint "eagle-import:R0603")
      (libsource (lib "eagle-import") (part "resistor_R-US_R0603"))
    )
    (comp (ref "R28")
      (value "4K7")
      (footprint "eagle-import:R0603")
      (libsource (lib "eagle-import") (part "resistor_R-US_R0603"))
    )
    (comp (ref "R29")
      (value "56r")
      (footprint "eagle-import:R0603")
      (libsource (lib "eagle-import") (part "resistor_R-US_R0603"))
    )
    (comp (ref "R30")
      (value "3.3K")
      (footprint "eagle-import:R0603")
      (libsource (lib "eagle-import") (part "resistor_R-US_R0603"))
    )
    (comp (ref "R31")
      (value "4K7")
      (footprint "eagle-import:R0603")
      (libsource (lib "eagle-import") (part "resistor_R-US_R0603"))
    )
    (comp (ref "R32")
      (value "4K7")
      (footprint "eagle-import:R0603")
      (libsource (lib "eagle-import") (part "resistor_R-US_R0603"))
    )
    (comp (ref "R33")
      (value "1K")
      (footprint "eagle-import:R0603")
      (libsource (lib "eagle-import") (part "resistor_R-US_R0603"))
    )
    (comp (ref "R34")
      (value "1K")
      (footprint "eagle-import:R0603")
      (libsource (lib "eagle-import") (part "resistor_R-US_R0603"))
    )
    (comp (ref "R35")
      (value "1K")
      (footprint "eagle-import:R0603")
      (libsource (lib "eagle-import") (part "resistor_R-US_R0603"))
    )
    (comp (ref "R36")
      (value "4K7")
      (footprint "eagle-import:R0603")
      (libsource (lib "eagle-import") (part "resistor_R-US_R0603"))
    )
    (comp (ref "R37")
      (value "4K7")
      (footprint "eagle-import:R0603")
      (libsource (lib "eagle-import") (part "resistor_R-US_R0603"))
    )
    (comp (ref "R38")
      (value "4K7")
      (footprint "eagle-import:R0603")
      (libsource (lib "eagle-import") (part "resistor_R-US_R0603"))
    )
    (comp (ref "R39")
      (value "4K7")
      (footprint "eagle-import:R0603")
      (libsource (lib "eagle-import") (part "resistor_R-US_R0603"))
    )
    (comp (ref "R40")
      (value "1.8K")
      (footprint "eagle-import:R0603")
      (libsource (lib "eagle-import") (part "resistor_R-US_R0603"))
    )
    (comp (ref "R41")
      (value "1.8K")
      (footprint "eagle-import:R0603")
      (libsource (lib "eagle-import") (part "resistor_R-US_R0603"))
    )
    (comp (ref "R42")
      (value "10r")
      (footprint "eagle-import:R0603")
      (libsource (lib "eagle-import") (part "resistor_R-US_R0603"))
    )
    (comp (ref "R43")
      (value "100K")
      (footprint "eagle-import:R0603")
      (libsource (lib "eagle-import") (part "resistor_R-US_R0603"))
    )
    (comp (ref "R44")
      (value "10K")
      (footprint "eagle-import:R0603")
      (libsource (lib "eagle-import") (part "resistor_R-US_R0603"))
    )
    (comp (ref "R45")
      (value "10K")
      (footprint "eagle-import:R0603")
      (libsource (lib "eagle-import") (part "resistor_R-US_R0603"))
    )
    (comp (ref "R46")
      (value "10K")
      (footprint "eagle-import:R0603")
      (libsource (lib "eagle-import") (part "resistor_R-US_R0603"))
    )
    (comp (ref "R47")
      (value "10K")
      (footprint "eagle-import:R0603")
      (libsource (lib "eagle-import") (part "resistor_R-US_R0603"))
    )
    (comp (ref "R48")
      (value "10r")
      (footprint "eagle-import:R0603")
      (libsource (lib "eagle-import") (part "resistor_R-US_R0603"))
    )
    (comp (ref "R49")
      (value "100K")
      (footprint "eagle-import:R0603")
      (libsource (lib "eagle-import") (part "resistor_R-US_R0603"))
    )
    (comp (ref "R50")
      (value "1.8K")
      (footprint "eagle-import:R0603")
      (libsource (lib "eagle-import") (part "resistor_R-US_R0603"))
    )
    (comp (ref "R51")
      (value "10r")
      (footprint "eagle-import:R0603")
      (libsource (lib "eagle-import") (part "resistor_R-US_R0603"))
    )
    (comp (ref "R52")
      (value "100K")
      (footprint "eagle-import:R0603")
      (libsource (lib "eagle-import") (part "resistor_R-US_R0603"))
    )
    (comp (ref "R53")
      (value "10r")
      (footprint "eagle-import:R0603")
      (libsource (lib "eagle-import") (part "resistor_R-US_R0603"))
    )
    (comp (ref "R54")
      (value "100K")
      (footprint "eagle-import:R0603")
      (libsource (lib "eagle-import") (part "resistor_R-US_R0603"))
    )
    (comp (ref "R55")
      (value "1.8K")
      (footprint "eagle-import:R0603")
      (libsource (lib "eagle-import") (part "resistor_R-US_R0603"))
    )
    (comp (ref "R56")
      (value "10r")
      (footprint "eagle-import:R0603")
      (libsource (lib "eagle-import") (part "resistor_R-US_R0603"))
    )
    (comp (ref "R57")
      (value "100K")
      (footprint "eagle-import:R0603")
      (libsource (lib "eagle-import") (part "resistor_R-US_R0603"))
    )
    (comp (ref "R58")
      (value "1.8K")
      (footprint "eagle-import:R0603")
      (libsource (lib "eagle-import") (part "resistor_R-US_R0603"))
    )
    (comp (ref "R59")
      (value "100K")
      (footprint "eagle-import:R0603")
      (libsource (lib "eagle-import") (part "resistor_R-US_R0603"))
    )
    (comp (ref "R60")
      (value "100K")
      (footprint "eagle-import:R0603")
      (libsource (lib "eagle-import") (part "resistor_R-US_R0603"))
    )
    (comp (ref "R61")
      (value "100K")
      (footprint "eagle-import:R0603")
      (libsource (lib "eagle-import") (part "resistor_R-US_R0603"))
    )
    (comp (ref "R62")
      (value "100K")
      (footprint "eagle-import:R0603")
      (libsource (lib "eagle-import") (part "resistor_R-US_R0603"))
    )
    (comp (ref "R63")
      (value "100K")
      (footprint "eagle-import:R0603")
      (libsource (lib "eagle-import") (part "resistor_R-US_R0603"))
    )
    (comp (ref "R65")
      (value "56r")
      (footprint "eagle-import:R0603")
      (libsource (lib "eagle-import") (part "resistor_R-US_R0603"))
    )
    (comp (ref "R66")
      (value "56r")
      (footprint "eagle-import:R0603")
      (libsource (lib "eagle-import") (part "resistor_R-US_R0603"))
    )
    (comp (ref "R67")
      (value "56r")
      (footprint "eagle-import:R0603")
      (libsource (lib "eagle-import") (part "resistor_R-US_R0603"))
    )
    (comp (ref "R68")
      (value "56r")
      (footprint "eagle-import:R0603")
      (libsource (lib "eagle-import") (part "resistor_R-US_R0603"))
    )
    (comp (ref "R69")
      (value "1.8K")
      (footprint "eagle-import:R0603")
      (libsource (lib "eagle-import") (part "resistor_R-US_R0603"))
    )
    (comp (ref "R70")
      (value "10r")
      (footprint "eagle-import:R0603")
      (libsource (lib "eagle-import") (part "resistor_R-US_R0603"))
    )
    (comp (ref "R71")
      (value "100K")
      (footprint "eagle-import:R0603")
      (libsource (lib "eagle-import") (part "resistor_R-US_R0603"))
    )
    (comp (ref "R72")
      (value "1M")
      (footprint "eagle-import:R0402")
      (libsource (lib "eagle-import") (part "R-US_R0402"))
    )
    (comp (ref "R73")
      (value "10K")
      (footprint "eagle-import:R0603")
      (libsource (lib "eagle-import") (part "resistor_R-US_R0603"))
    )
    (comp (ref "RN5")
      (value "1k")
      (footprint "eagle-import:CAY16")
      (libsource (lib "eagle-import") (part "4R-NCAY16"))
    )
    (comp (ref "S1")
      (value "31-XX")
      (footprint "eagle-import:B3F-31XX")
      (libsource (lib "eagle-import") (part "31-XX"))
    )
    (comp (ref "TP0")
      (value "PTR1B1,27TH")
      (footprint "eagle-import:B1,27TH")
      (libsource (lib "eagle-import") (part "PTR1B1,27TH"))
    )
    (comp (ref "TP1")
      (value "PTR1B1,27TH")
      (footprint "eagle-import:B1,27TH")
      (libsource (lib "eagle-import") (part "PTR1B1,27TH"))
    )
    (comp (ref "TP2")
      (value "PTR1B1,27TH")
      (footprint "eagle-import:B1,27TH")
      (libsource (lib "eagle-import") (part "PTR1B1,27TH"))
    )
    (comp (ref "TP3")
      (value "PTR1B1,27TH")
      (footprint "eagle-import:B1,27TH")
      (libsource (lib "eagle-import") (part "PTR1B1,27TH"))
    )
    (comp (ref "TP4")
      (value "PTR1B1,27TH")
      (footprint "eagle-import:B1,27TH")
      (libsource (lib "eagle-import") (part "PTR1B1,27TH"))
    )
    (comp (ref "TP5")
      (value "PTR1B1,27TH")
      (footprint "eagle-import:B1,27TH")
      (libsource (lib "eagle-import") (part "PTR1B1,27TH"))
    )
    (comp (ref "TP6")
      (value "PTR1B1,27TH")
      (footprint "eagle-import:B1,27TH")
      (libsource (lib "eagle-import") (part "PTR1B1,27TH"))
    )
    (comp (ref "TP7")
      (value "PTR1B1,27TH")
      (footprint "eagle-import:B1,27TH")
      (libsource (lib "eagle-import") (part "PTR1B1,27TH"))
    )
    (comp (ref "TP8")
      (value "PTR1B1,27TH")
      (footprint "eagle-import:B1,27TH")
      (libsource (lib "eagle-import") (part "PTR1B1,27TH"))
    )
    (comp (ref "TP9")
      (value "PTR1B1,27TH")
      (footprint "eagle-import:B1,27TH")
      (libsource (lib "eagle-import") (part "PTR1B1,27TH"))
    )
    (comp (ref "TP10")
      (value "PTR1B1,27TH")
      (footprint "eagle-import:B1,27TH")
      (libsource (lib "eagle-import") (part "PTR1B1,27TH"))
    )
    (comp (ref "TP11")
      (value "PTR1B1,27TH")
      (footprint "eagle-import:B1,27TH")
      (libsource (lib "eagle-import") (part "PTR1B1,27TH"))
    )
    (comp (ref "TP12")
      (value "PTR1B1,27TH")
      (footprint "eagle-import:B1,27TH")
      (libsource (lib "eagle-import") (part "PTR1B1,27TH"))
    )
    (comp (ref "TP13")
      (value "PTR1B1,27TH")
      (footprint "eagle-import:B1,27TH")
      (libsource (lib "eagle-import") (part "PTR1B1,27TH"))
    )
    (comp (ref "TP14")
      (value "PTR1B1,27TH")
      (footprint "eagle-import:B1,27TH")
      (libsource (lib "eagle-import") (part "PTR1B1,27TH"))
    )
    (comp (ref "TP15")
      (value "PTR1B1,27TH")
      (footprint "eagle-import:B1,27TH")
      (libsource (lib "eagle-import") (part "PTR1B1,27TH"))
    )
    (comp (ref "TP16")
      (value "PTR1B1,27TH")
      (footprint "eagle-import:B1,27TH")
      (libsource (lib "eagle-import") (part "PTR1B1,27TH"))
    )
    (comp (ref "TP17")
      (value "PTR1B1,27TH")
      (footprint "eagle-import:B1,27TH")
      (libsource (lib "eagle-import") (part "PTR1B1,27TH"))
    )
    (comp (ref "TP18")
      (value "PTR1B1,27TH")
      (footprint "eagle-import:B1,27TH")
      (libsource (lib "eagle-import") (part "PTR1B1,27TH"))
    )
    (comp (ref "TP19")
      (value "PTR1B1,27TH")
      (footprint "eagle-import:B1,27TH")
      (libsource (lib "eagle-import") (part "PTR1B1,27TH"))
    )
    (comp (ref "TP20")
      (value "PTR1B1,27")
      (footprint "eagle-import:B1,27")
      (libsource (lib "eagle-import") (part "PTR1B1,27"))
    )
    (comp (ref "TP21")
      (value "PTR1B1,27")
      (footprint "eagle-import:B1,27")
      (libsource (lib "eagle-import") (part "PTR1B1,27"))
    )
    (comp (ref "TP22")
      (value "PTR1B1,27")
      (footprint "eagle-import:B1,27")
      (libsource (lib "eagle-import") (part "PTR1B1,27"))
    )
    (comp (ref "TP23")
      (value "PTR1B1,27")
      (footprint "eagle-import:B1,27")
      (libsource (lib "eagle-import") (part "PTR1B1,27"))
    )
    (comp (ref "TP24")
      (value "GND")
      (footprint "eagle-import:1X01")
      (libsource (lib "eagle-import") (part "PINHD-1X1"))
    )
    (comp (ref "U1")
      (value "ATMEGA32U2-MUR")
      (footprint "eagle-import:QFN32TROUND")
      (libsource (lib "eagle-import") (part "ATMEGA16U2-MU2"))
    )
    (comp (ref "U2")
      (value "ATMEGA2560-16AU")
      (footprint "eagle-import:TQFP100")
      (libsource (lib "eagle-import") (part "ATMEGA2560AU2560-16"))
    )
    (comp (ref "U3")
      (value "LM22675")
      (footprint "eagle-import:SOIC127P600X170-9N")
      (libsource (lib "eagle-import") (part "LM22675"))
    )
    (comp (ref "U4")
      (value "AD5206")
      (footprint "eagle-import:TSSOP24")
      (libsource (lib "eagle-import") (part "AD5206"))
    )
    (comp (ref "U5")
      (value "A4982")
      (footprint "eagle-import:QFN32TROUND")
      (libsource (lib "eagle-import") (part "A4982QFN32ROUNDPADS"))
    )
    (comp (ref "U6")
      (value "A4982")
      (footprint "eagle-import:QFN32TROUND")
      (libsource (lib "eagle-import") (part "A4982QFN32ROUNDPADS"))
    )
    (comp (ref "U7")
      (value "A4982")
      (footprint "eagle-import:QFN32TROUND")
      (libsource (lib "eagle-import") (part "A4982QFN32ROUNDPADS"))
    )
    (comp (ref "U8")
      (value "A4982")
      (footprint "eagle-import:QFN32TROUND")
      (libsource (lib "eagle-import") (part "A4982QFN32ROUNDPADS"))
    )
    (comp (ref "U9")
      (value "A4982")
      (footprint "eagle-import:QFN32TROUND")
      (libsource (lib "eagle-import") (part "A4982QFN32ROUNDPADS"))
    )
    (comp (ref "U10")
      (value "ADUM7441")
      (footprint "eagle-import:QSOP16")
      (libsource (lib "eagle-import") (part "ADUM7441"))
    )
    (comp (ref "X1")
      (value "C-GRID-02-70543")
      (footprint "eagle-import:70543-02")
      (libsource (lib "eagle-import") (part "C-GRID-02-70543"))
    )
    (comp (ref "X2")
      (value "USB B-TH")
      (footprint "eagle-import:PN61729")
      (libsource (lib "eagle-import") (part "PN61729"))
    )
    (comp (ref "X3")
      (value "C-GRID-02-70543")
      (footprint "eagle-import:70543-02")
      (libsource (lib "eagle-import") (part "C-GRID-02-70543"))
    )
    (comp (ref "X4")
      (value "C-GRID-04-70543")
      (footprint "eagle-import:4POL254")
      (libsource (lib "eagle-import") (part "MPT4"))
    )
    (comp (ref "X5")
      (value "C-GRID-02-70543")
      (footprint "eagle-import:70543-02")
      (libsource (lib "eagle-import") (part "C-GRID-02-70543"))
    )
    (comp (ref "X6")
      (value "C-GRID-04-70543")
      (footprint "eagle-import:4POL254")
      (libsource (lib "eagle-import") (part "MPT4"))
    )
    (comp (ref "X7")
      (value "C-GRID-04-70543")
      (footprint "eagle-import:4POL254")
      (libsource (lib "eagle-import") (part "MPT4"))
    )
    (comp (ref "X8")
      (value "C-GRID-04-70543")
      (footprint "eagle-import:4POL254")
      (libsource (lib "eagle-import") (part "MPT4"))
    )
    (comp (ref "X9")
      (value "C-GRID-02-70543")
      (footprint "eagle-import:70543-02")
      (fields (field (name "OC_FARNELL") "unknown") (field (name "OC_NEWARK") "unknown"))
      (libsource (lib "eagle-import") (part "C-GRID-02-70543"))
    )
    (comp (ref "X10")
      (value "C-GRID-04-70543")
      (footprint "eagle-import:70543-04")
      (libsource (lib "eagle-import") (part "C-GRID-04-70543"))
    )
    (comp (ref "X11")
      (value "MSTBV10")
      (footprint "eagle-import:MSTBV10")
      (fields (field (name "MPN") "MSTBV 2,5/10-GF-5.08"))
      (libsource (lib "eagle-import") (part "MSTBV10"))
    )
    (comp (ref "X12")
      (value "SPI")
      (footprint "eagle-import:2X4")
      (libsource (lib "eagle-import") (part "M04X2"))
    )
    (comp (ref "X13")
      (value "EXT-2")
      (footprint "eagle-import:2X10")
      (libsource (lib "eagle-import") (part "M10X2"))
    )
    (comp (ref "X14")
      (value "C-GRID-04-70543")
      (footprint "eagle-import:4POL254")
      (libsource (lib "eagle-import") (part "MPT4"))
    )
    (comp (ref "X15")
      (value "C-GRID-04-70543")
      (footprint "eagle-import:4POL254")
      (fields (field (name "OC_FARNELL") "unknown") (field (name "OC_NEWARK") "unknown"))
      (libsource (lib "eagle-import") (part "MPT4"))
    )
    (comp (ref "X16")
      (value "32u2 EXT")
      (footprint "eagle-import:2X8")
      (libsource (lib "eagle-import") (part "M08X2"))
    )
    (comp (ref "X17")
      (value "3x2M")
      (footprint "eagle-import:2X03")
      (libsource (lib "eagle-import") (part "PINHD-2X3"))
    )
    (comp (ref "X18")
      (value "3x2M")
      (footprint "eagle-import:2X03")
      (libsource (lib "eagle-import") (part "PINHD-2X3"))
    )
    (comp (ref "X20")
      (value "MX1")
      (footprint "eagle-import:1X05")
      (libsource (lib "eagle-import") (part "M05PTH"))
    )
    (comp (ref "X21")
      (value "C-GRID-03-70543")
      (footprint "eagle-import:70543-03")
      (libsource (lib "eagle-import") (part "C-GRID-03-70543"))
    )
    (comp (ref "X22")
      (value "C-GRID-03-70543")
      (footprint "eagle-import:70543-03")
      (libsource (lib "eagle-import") (part "C-GRID-03-70543"))
    )
    (comp (ref "X23")
      (value "C-GRID-03-70543")
      (footprint "eagle-import:70543-03")
      (libsource (lib "eagle-import") (part "C-GRID-03-70543"))
    )
    (comp (ref "X24")
      (value "C-GRID-03-70543")
      (footprint "eagle-import:70543-03")
      (libsource (lib "eagle-import") (part "C-GRID-03-70543"))
    )
    (comp (ref "X25")
      (value "C-GRID-03-70543")
      (footprint "eagle-import:70543-03")
      (libsource (lib "eagle-import") (part "C-GRID-03-70543"))
    )
    (comp (ref "X26")
      (value "C-GRID-03-70543")
      (footprint "eagle-import:70543-03")
      (libsource (lib "eagle-import") (part "C-GRID-03-70543"))
    )
    (comp (ref "X27")
      (value "C-GRID-02-70543")
      (footprint "eagle-import:70543-02")
      (libsource (lib "eagle-import") (part "C-GRID-02-70543"))
    )
    (comp (ref "X28")
      (value "C-GRID-02-70543")
      (footprint "eagle-import:70543-02")
      (libsource (lib "eagle-import") (part "C-GRID-02-70543"))
    )
    (comp (ref "X29")
      (value "C-GRID-02-70543")
      (footprint "eagle-import:70543-02")
      (libsource (lib "eagle-import") (part "C-GRID-02-70543"))
    )
    (comp (ref "X30")
      (value "C-GRID-02-70543")
      (footprint "eagle-import:70543-02")
      (libsource (lib "eagle-import") (part "C-GRID-02-70543"))
    )
    (comp (ref "X31")
      (value "MX2")
      (footprint "eagle-import:1X05")
      (libsource (lib "eagle-import") (part "M05PTH"))
    )
    (comp (ref "X32")
      (value "MX3")
      (footprint "eagle-import:1X05")
      (libsource (lib "eagle-import") (part "M05PTH"))
    )
    (comp (ref "X33")
      (value "MSTBA6")
      (footprint "eagle-import:MSTBA6")
      (fields (field (name "MF") "FARNELL") (field (name "MPN") "1757284"))
      (libsource (lib "eagle-import") (part "MSTBA6"))
    )
    (comp (ref "X34")
      (value "PWM_EXT")
      (footprint "eagle-import:1X06")
      (libsource (lib "eagle-import") (part "M06SIP"))
    )
    (comp (ref "X35")
      (value "M02PTH")
      (footprint "eagle-import:1X02")
      (libsource (lib "eagle-import") (part "M02PTH"))
    )
    (comp (ref "X36")
      (value "M02PTH")
      (footprint "eagle-import:1X02")
      (libsource (lib "eagle-import") (part "M02PTH"))
    )
    (comp (ref "X37")
      (value "M02PTH")
      (footprint "eagle-import:1X02")
      (libsource (lib "eagle-import") (part "M02PTH"))
    )
    (comp (ref "X38")
      (value "M02PTH")
      (footprint "eagle-import:1X02")
      (libsource (lib "eagle-import") (part "M02PTH"))
    )
    (comp (ref "X39")
      (value "M05X2PTH")
      (footprint "eagle-import:AVR_ICSP")
      (libsource (lib "eagle-import") (part "M05X2PTH"))
    )
    (comp (ref "X40")
      (value "Analog")
      (footprint "eagle-import:2X4")
      (libsource (lib "eagle-import") (part "M04X2"))
    )
    (comp (ref "Y1")
      (value "16MHz KX-7")
      (footprint "eagle-import:CRYSTAL-3.2-2.5")
      (libsource (lib "eagle-import") (part "CRYSTAL-3.2-2.5"))
    )
    (comp (ref "Y2")
      (value "16MHz KX-7")
      (footprint "eagle-import:CRYSTAL-3.2-2.5")
      (libsource (lib "eagle-import") (part "CRYSTAL-3.2-2.5"))
    )
    (comp (ref "Z1")
      (value "CG0603MLC-05E")
      (footprint "eagle-import:R0603")
      (libsource (lib "eagle-import") (part "resistor_R-US_R0603"))
    )
    (comp (ref "Z2")
      (value "CG0603MLC-05E")
      (footprint "eagle-import:R0603")
      (libsource (lib "eagle-import") (part "resistor_R-US_R0603"))
    )
  )
  (nets
    (net (code "1") (name "+12V") (class "Default")
      (node (ref "C27") (pin "1") (pinfunction "1_1") (pintype "passive"))
      (node (ref "C29") (pin "1") (pinfunction "1_1") (pintype "passive"))
      (node (ref "C32") (pin "1") (pinfunction "1_1") (pintype "passive"))
      (node (ref "C34") (pin "1") (pinfunction "1_1") (pintype "passive"))
      (node (ref "C37") (pin "1") (pinfunction "1_1") (pintype "passive"))
      (node (ref "C39") (pin "1") (pinfunction "1_1") (pintype "passive"))
      (node (ref "C42") (pin "1") (pinfunction "1_1") (pintype "passive"))
      (node (ref "C44") (pin "1") (pinfunction "1_1") (pintype "passive"))
      (node (ref "C47") (pin "1") (pinfunction "1_1") (pintype "passive"))
      (node (ref "C49") (pin "1") (pinfunction "1_1") (pintype "passive"))
      (node (ref "C71") (pin "1") (pinfunction "1_1") (pintype "passive"))
      (node (ref "C72") (pin "1") (pinfunction "1_1") (pintype "passive"))
      (node (ref "C73") (pin "1") (pinfunction "1_1") (pintype "passive"))
      (node (ref "C74") (pin "1") (pinfunction "1_1") (pintype "passive"))
      (node (ref "C75") (pin "1") (pinfunction "1_1") (pintype "passive"))
      (node (ref "C76") (pin "+") (pinfunction "+_+") (pintype "passive"))
      (node (ref "D2") (pin "C") (pinfunction "C_C") (pintype "passive"))
      (node (ref "F2") (pin "P$2") (pinfunction "P$2_P$2") (pintype "bidirectional"))
      (node (ref "U5") (pin "22") (pinfunction "VBB_22") (pintype "power_in"))
      (node (ref "U5") (pin "3") (pinfunction "VBB1_3") (pintype "power_in"))
      (node (ref "U6") (pin "22") (pinfunction "VBB_22") (pintype "power_in"))
      (node (ref "U6") (pin "3") (pinfunction "VBB1_3") (pintype "power_in"))
      (node (ref "U7") (pin "22") (pinfunction "VBB_22") (pintype "power_in"))
      (node (ref "U7") (pin "3") (pinfunction "VBB1_3") (pintype "power_in"))
      (node (ref "U8") (pin "22") (pinfunction "VBB_22") (pintype "power_in"))
      (node (ref "U8") (pin "3") (pinfunction "VBB1_3") (pintype "power_in"))
      (node (ref "U9") (pin "22") (pinfunction "VBB_22") (pintype "power_in"))
      (node (ref "U9") (pin "3") (pinfunction "VBB1_3") (pintype "power_in"))
      (node (ref "X30") (pin "2") (pinfunction "S_2") (pintype "passive"))
    )
    (net (code "2") (name "+12V2") (class "Default")
      (node (ref "C40") (pin "1") (pinfunction "1_1") (pintype "passive"))
      (node (ref "C45") (pin "1") (pinfunction "1_1") (pintype "passive"))
      (node (ref "C60") (pin "1") (pinfunction "1_1") (pintype "passive"))
      (node (ref "C65") (pin "+") (pinfunction "+_+") (pintype "passive"))
      (node (ref "D1") (pin "C") (pinfunction "C_C") (pintype "passive"))
      (node (ref "D3") (pin "C") (pinfunction "C_C") (pintype "passive"))
      (node (ref "D6") (pin "C") (pinfunction "C_C") (pintype "passive"))
      (node (ref "D8") (pin "C") (pinfunction "C_C") (pintype "passive"))
      (node (ref "F3") (pin "P$2") (pinfunction "P$2_P$2") (pintype "bidirectional"))
      (node (ref "R3") (pin "2") (pinfunction "2_2") (pintype "passive"))
      (node (ref "R40") (pin "2") (pinfunction "2_2") (pintype "passive"))
      (node (ref "R41") (pin "2") (pinfunction "2_2") (pintype "passive"))
      (node (ref "R50") (pin "2") (pinfunction "2_2") (pintype "passive"))
      (node (ref "R55") (pin "2") (pinfunction "2_2") (pintype "passive"))
      (node (ref "R69") (pin "2") (pinfunction "2_2") (pintype "passive"))
      (node (ref "R73") (pin "2") (pinfunction "2_2") (pintype "passive"))
      (node (ref "U3") (pin "7") (pinfunction "VIN_7") (pintype "power_in"))
      (node (ref "X11") (pin "2") (pinfunction "1_2") (pintype "passive"))
      (node (ref "X11") (pin "4") (pinfunction "1_4") (pintype "passive"))
      (node (ref "X11") (pin "6") (pinfunction "1_6") (pintype "passive"))
      (node (ref "X11") (pin "8") (pinfunction "1_8") (pintype "passive"))
      (node (ref "X35") (pin "2") (pinfunction "2_2") (pintype "passive"))
      (node (ref "X36") (pin "2") (pinfunction "2_2") (pintype "passive"))
      (node (ref "X37") (pin "2") (pinfunction "2_2") (pintype "passive"))
      (node (ref "X9") (pin "2") (pinfunction "S_2") (pintype "passive"))
    )
    (net (code "3") (name "+12V3") (class "Default")
      (node (ref "C54") (pin "1") (pinfunction "1_1") (pintype "passive"))
      (node (ref "C62") (pin "1") (pinfunction "1_1") (pintype "passive"))
      (node (ref "C66") (pin "+") (pinfunction "+_+") (pintype "passive"))
      (node (ref "D10") (pin "C") (pinfunction "C_C") (pintype "passive"))
      (node (ref "D7") (pin "C") (pinfunction "C_C") (pintype "passive"))
      (node (ref "F4") (pin "P$2") (pinfunction "2_P$2") (pintype "passive"))
      (node (ref "R58") (pin "2") (pinfunction "2_2") (pintype "passive"))
      (node (ref "X11") (pin "10") (pinfunction "1_10") (pintype "passive"))
      (node (ref "X38") (pin "2") (pinfunction "2_2") (pintype "passive"))
    )
    (net (code "4") (name "/AREF") (class "Default")
      (node (ref "C6") (pin "1") (pinfunction "1_1") (pintype "passive"))
      (node (ref "U2") (pin "98") (pinfunction "AREF_98") (pintype "bidirectional"))
    )
    (net (code "5") (name "/BED-HEAT") (class "Default")
      (node (ref "R56") (pin "1") (pinfunction "1_1") (pintype "passive"))
      (node (ref "R57") (pin "1") (pinfunction "1_1") (pintype "passive"))
      (node (ref "U2") (pin "7") (pinfunction "(OC3C/INT5)PE5_7") (pintype "bidirectional"))
    )
    (net (code "6") (name "/D+") (class "Default")
      (node (ref "R2") (pin "1") (pinfunction "1_1") (pintype "passive"))
      (node (ref "X2") (pin "3") (pinfunction "3_3") (pintype "bidirectional"))
      (node (ref "Z2") (pin "2") (pinfunction "2_2") (pintype "passive"))
    )
    (net (code "7") (name "/D-") (class "Default")
      (node (ref "R1") (pin "1") (pinfunction "1_1") (pintype "passive"))
      (node (ref "X2") (pin "2") (pinfunction "2_2") (pintype "bidirectional"))
      (node (ref "Z1") (pin "2") (pinfunction "2_2") (pintype "passive"))
    )
    (net (code "8") (name "/DP-SS") (class "Default")
      (node (ref "U2") (pin "50") (pinfunction "(T0)PD7_50") (pintype "bidirectional"))
      (node (ref "U4") (pin "P05") (pinfunction "_CS_P05") (pintype "bidirectional"))
    )
    (net (code "9") (name "/DTR") (class "Default")
      (node (ref "JP2") (pin "1") (pinfunction "1_1") (pintype "passive"))
      (node (ref "JP2") (pin "2") (pinfunction "2_2") (pintype "passive"))
      (node (ref "RN5") (pin "5") (pinfunction "2_5") (pintype "passive"))
      (node (ref "U1") (pin "13") (pinfunction "(CTS/HWB/AIN6/TO/INT7)PD7_13") (pintype "bidirectional"))
      (node (ref "U10") (pin "3") (pinfunction "VIA_3") (pintype "bidirectional"))
    )
    (net (code "10") (name "/E0-DIR") (class "Default")
      (node (ref "TP11") (pin "TP") (pinfunction "TP_TP") (pintype "input"))
      (node (ref "U2") (pin "41") (pinfunction "PL6_41") (pintype "bidirectional"))
      (node (ref "U8") (pin "20") (pinfunction "DIR_20") (pintype "input"))
    )
    (net (code "11") (name "/E0-EN") (class "Default")
      (node (ref "R62") (pin "2") (pinfunction "2_2") (pintype "passive"))
      (node (ref "TP14") (pin "TP") (pinfunction "TP_TP") (pintype "input"))
      (node (ref "U2") (pin "74") (pinfunction "(AD4)PA4_74") (pintype "bidirectional"))
      (node (ref "U8") (pin "5") (pinfunction "EN_5") (pintype "input"))
    )
    (net (code "12") (name "/E0-MS1") (class "Default")
      (node (ref "U2") (pin "86") (pinfunction "PK3(ADC11/PCINT19)_86") (pintype "bidirectional"))
      (node (ref "U8") (pin "11") (pinfunction "MS1_11") (pintype "input"))
    )
    (net (code "13") (name "/E0-MS2") (class "Default")
      (node (ref "U2") (pin "85") (pinfunction "PK4(ADC12/PCINT20)_85") (pintype "bidirectional"))
      (node (ref "U8") (pin "12") (pinfunction "MS2_12") (pintype "input"))
    )
    (net (code "14") (name "/E0-REF") (class "Default")
      (node (ref "TP12") (pin "TP") (pinfunction "TP_TP") (pintype "input"))
      (node (ref "U4") (pin "P17") (pinfunction "W1_P17") (pintype "bidirectional"))
      (node (ref "U8") (pin "18") (pinfunction "REF_18") (pintype "input"))
    )
    (net (code "15") (name "/E0-STEP") (class "Default")
      (node (ref "TP13") (pin "TP") (pinfunction "TP_TP") (pintype "input"))
      (node (ref "U2") (pin "56") (pinfunction "(A11)PC3_56") (pintype "bidirectional"))
      (node (ref "U8") (pin "17") (pinfunction "STEP_17") (pintype "input"))
    )
    (net (code "16") (name "/E1-DIR") (class "Default")
      (node (ref "TP15") (pin "TP") (pinfunction "TP_TP") (pintype "input"))
      (node (ref "U2") (pin "42") (pinfunction "PL7_42") (pintype "bidirectional"))
      (node (ref "U9") (pin "20") (pinfunction "DIR_20") (pintype "input"))
    )
    (net (code "17") (name "/E1-EN") (class "Default")
      (node (ref "R63") (pin "2") (pinfunction "2_2") (pintype "passive"))
      (node (ref "TP18") (pin "TP") (pinfunction "TP_TP") (pintype "input"))
      (node (ref "U2") (pin "75") (pinfunction "(AD3)PA3_75") (pintype "bidirectional"))
      (node (ref "U9") (pin "5") (pinfunction "EN_5") (pintype "input"))
    )
    (net (code "18") (name "/E1-MS1") (class "Default")
      (node (ref "U2") (pin "88") (pinfunction "PK1(ADC9/PCINT17)_88") (pintype "bidirectional"))
      (node (ref "U9") (pin "11") (pinfunction "MS1_11") (pintype "input"))
    )
    (net (code "19") (name "/E1-MS2") (class "Default")
      (node (ref "U2") (pin "87") (pinfunction "PK2(ADC10/PCINT18)_87") (pintype "bidirectional"))
      (node (ref "U9") (pin "12") (pinfunction "MS2_12") (pintype "input"))
    )
    (net (code "20") (name "/E1-REF") (class "Default")
      (node (ref "TP17") (pin "TP") (pinfunction "TP_TP") (pintype "input"))
      (node (ref "U4") (pin "P20") (pinfunction "W2_P20") (pintype "bidirectional"))
      (node (ref "U9") (pin "18") (pinfunction "REF_18") (pintype "input"))
    )
    (net (code "21") (name "/E1-STEP") (class "Default")
      (node (ref "TP16") (pin "TP") (pinfunction "TP_TP") (pintype "input"))
      (node (ref "U2") (pin "57") (pinfunction "(A12)PC4_57") (pintype "bidirectional"))
      (node (ref "U9") (pin "17") (pinfunction "STEP_17") (pintype "input"))
    )
    (net (code "22") (name "/FAN-0") (class "Default")
      (node (ref "R48") (pin "1") (pinfunction "1_1") (pintype "passive"))
      (node (ref "R49") (pin "1") (pinfunction "1_1") (pintype "passive"))
      (node (ref "U2") (pin "17") (pinfunction "PH5(OC4C)_17") (pintype "bidirectional"))
    )
    (net (code "23") (name "/FAN-1") (class "Default")
      (node (ref "R53") (pin "1") (pinfunction "1_1") (pintype "passive"))
      (node (ref "R54") (pin "1") (pinfunction "1_1") (pintype "passive"))
      (node (ref "U2") (pin "15") (pinfunction "PH3(OC4A)_15") (pintype "bidirectional"))
    )
    (net (code "24") (name "/FAN-2") (class "Default")
      (node (ref "R70") (pin "1") (pinfunction "1_1") (pintype "passive"))
      (node (ref "R71") (pin "1") (pinfunction "1_1") (pintype "passive"))
      (node (ref "U2") (pin "6") (pinfunction "(OC3B/INT4)PE4_6") (pintype "bidirectional"))
      (node (ref "X34") (pin "4") (pinfunction "4_4") (pintype "passive"))
    )
    (net (code "25") (name "/HEAT-0") (class "Default")
      (node (ref "R42") (pin "1") (pinfunction "1_1") (pintype "passive"))
      (node (ref "R43") (pin "1") (pinfunction "1_1") (pintype "passive"))
      (node (ref "U2") (pin "18") (pinfunction "PH6(OC2B)_18") (pintype "bidirectional"))
    )
    (net (code "26") (name "/HEAT-1") (class "Default")
      (node (ref "R51") (pin "1") (pinfunction "1_1") (pintype "passive"))
      (node (ref "R52") (pin "1") (pinfunction "1_1") (pintype "passive"))
      (node (ref "U2") (pin "16") (pinfunction "PH4(OC4B)_16") (pintype "bidirectional"))
    )
    (net (code "27") (name "/L13") (class "Default")
      (node (ref "R33") (pin "1") (pinfunction "1_1") (pintype "passive"))
      (node (ref "U2") (pin "26") (pinfunction "(OC0A/OC1C/PCINT7)PB7_26") (pintype "bidirectional"))
      (node (ref "X34") (pin "3") (pinfunction "3_3") (pintype "passive"))
    )
    (net (code "28") (name "/MISO2") (class "Default")
      (node (ref "U1") (pin "17") (pinfunction "(PD0/MISO/PCINT3)PB3_17") (pintype "bidirectional"))
      (node (ref "X17") (pin "1") (pinfunction "1_1") (pintype "passive"))
    )
    (net (code "29") (name "/MOSI2") (class "Default")
      (node (ref "U1") (pin "16") (pinfunction "(PDI/MOSI/PCINT2)PB2_16") (pintype "bidirectional"))
      (node (ref "X17") (pin "4") (pinfunction "4_4") (pintype "passive"))
    )
    (net (code "30") (name "/N$96") (class "Default")
      (node (ref "U4") (pin "P14") (pinfunction "W3_P14") (pintype "bidirectional"))
    )
    (net (code "31") (name "/OVREF") (class "Default")
      (node (ref "D11") (pin "C") (pinfunction "C_C") (pintype "passive"))
      (node (ref "D12") (pin "C") (pinfunction "C_C") (pintype "passive"))
      (node (ref "D14") (pin "C") (pinfunction "C_C") (pintype "passive"))
      (node (ref "D16") (pin "C") (pinfunction "C_C") (pintype "passive"))
      (node (ref "D18") (pin "C") (pinfunction "C_C") (pintype "passive"))
      (node (ref "R73") (pin "1") (pinfunction "1_1") (pintype "passive"))
    )
    (net (code "32") (name "/PA0") (class "Default")
      (node (ref "U2") (pin "78") (pinfunction "(AD0)PA0_78") (pintype "bidirectional"))
      (node (ref "X20") (pin "3") (pinfunction "3_3") (pintype "passive"))
    )
    (net (code "33") (name "/PA1") (class "Default")
      (node (ref "U2") (pin "77") (pinfunction "(AD1)PA1_77") (pintype "bidirectional"))
      (node (ref "X25") (pin "1") (pinfunction "S_1") (pintype "passive"))
      (node (ref "X31") (pin "3") (pinfunction "3_3") (pintype "passive"))
    )
    (net (code "34") (name "/PA2") (class "Default")
      (node (ref "U2") (pin "76") (pinfunction "(AD2)PA2_76") (pintype "bidirectional"))
      (node (ref "X26") (pin "1") (pinfunction "S_1") (pintype "passive"))
      (node (ref "X32") (pin "3") (pinfunction "3_3") (pintype "passive"))
    )
    (net (code "35") (name "/PB0_SS") (class "Default")
      (node (ref "U2") (pin "19") (pinfunction "(SS/PCINT0)PB0_19") (pintype "bidirectional"))
      (node (ref "X12") (pin "6") (pinfunction "6_6") (pintype "passive"))
    )
    (net (code "36") (name "/PB1_SCK") (class "Default")
      (node (ref "U2") (pin "20") (pinfunction "(SCK/PCINT1)PB1_20") (pintype "bidirectional"))
      (node (ref "U4") (pin "P08") (pinfunction "SCK_P08") (pintype "bidirectional"))
      (node (ref "X12") (pin "5") (pinfunction "5_5") (pintype "passive"))
      (node (ref "X18") (pin "3") (pinfunction "3_3") (pintype "passive"))
    )
    (net (code "37") (name "/PB2_MOSI") (class "Default")
      (node (ref "U2") (pin "21") (pinfunction "(MOSI/PCINT2)PB2_21") (pintype "bidirectional"))
      (node (ref "U4") (pin "P07") (pinfunction "SDI_P07") (pintype "bidirectional"))
      (node (ref "X12") (pin "4") (pinfunction "4_4") (pintype "passive"))
      (node (ref "X18") (pin "4") (pinfunction "4_4") (pintype "passive"))
    )
    (net (code "38") (name "/PB3_MISO") (class "Default")
      (node (ref "U2") (pin "22") (pinfunction "(MISO/PCINT3)PB3_22") (pintype "bidirectional"))
      (node (ref "X12") (pin "3") (pinfunction "3_3") (pintype "passive"))
      (node (ref "X18") (pin "1") (pinfunction "1_1") (pintype "passive"))
    )
    (net (code "39") (name "/PC5") (class "Default")
      (node (ref "U2") (pin "58") (pinfunction "(A13)PC5_58") (pintype "bidirectional"))
      (node (ref "X20") (pin "4") (pinfunction "4_4") (pintype "passive"))
    )
    (net (code "40") (name "/PC6") (class "Default")
      (node (ref "U2") (pin "59") (pinfunction "(A14)PC6_59") (pintype "bidirectional"))
      (node (ref "X31") (pin "4") (pinfunction "4_4") (pintype "passive"))
    )
    (net (code "41") (name "/PC7") (class "Default")
      (node (ref "U2") (pin "60") (pinfunction "(A15)PC7_60") (pintype "bidirectional"))
      (node (ref "X24") (pin "1") (pinfunction "S_1") (pintype "passive"))
      (node (ref "X32") (pin "4") (pinfunction "4_4") (pintype "passive"))
    )
    (net (code "42") (name "/PD4") (class "Default")
      (node (ref "U2") (pin "47") (pinfunction "(ICP1)PD4_47") (pintype "bidirectional"))
      (node (ref "X13") (pin "14") (pinfunction "14_14") (pintype "passive"))
    )
    (net (code "43") (name "/PD5") (class "Default")
      (node (ref "U2") (pin "48") (pinfunction "(XCK1)PD5_48") (pintype "bidirectional"))
      (node (ref "X13") (pin "12") (pinfunction "12_12") (pintype "passive"))
    )
    (net (code "44") (name "/PD6") (class "Default")
      (node (ref "U2") (pin "49") (pinfunction "(T1)PD6_49") (pintype "bidirectional"))
      (node (ref "X13") (pin "10") (pinfunction "10_10") (pintype "passive"))
    )
    (net (code "45") (name "/PE2") (class "Default")
      (node (ref "U2") (pin "4") (pinfunction "(XCK0/AIN0)PE2_4") (pintype "bidirectional"))
      (node (ref "X13") (pin "20") (pinfunction "20_20") (pintype "passive"))
    )
    (net (code "46") (name "/PE3") (class "Default")
      (node (ref "U2") (pin "5") (pinfunction "(OC3A/AIN1)PE3_5") (pintype "bidirectional"))
      (node (ref "X34") (pin "5") (pinfunction "5_5") (pintype "passive"))
    )
    (net (code "47") (name "/PE6") (class "Default")
      (node (ref "U2") (pin "8") (pinfunction "(T3/INT6)PE6_8") (pintype "bidirectional"))
      (node (ref "X13") (pin "18") (pinfunction "18_18") (pintype "passive"))
    )
    (net (code "48") (name "/PE7") (class "Default")
      (node (ref "U2") (pin "9") (pinfunction "(CLKO/ICP3/INT7)PE7_9") (pintype "bidirectional"))
      (node (ref "X13") (pin "16") (pinfunction "16_16") (pintype "passive"))
    )
    (net (code "49") (name "/PF3") (class "Default")
      (node (ref "U2") (pin "94") (pinfunction "(ADC3)PF3_94") (pintype "bidirectional"))
      (node (ref "X40") (pin "4") (pinfunction "4_4") (pintype "passive"))
    )
    (net (code "50") (name "/PF4") (class "Default")
      (node (ref "U2") (pin "93") (pinfunction "(ADC4/TCK)PF4_93") (pintype "bidirectional"))
      (node (ref "X40") (pin "6") (pinfunction "6_6") (pintype "passive"))
    )
    (net (code "51") (name "/PF5") (class "Default")
      (node (ref "U2") (pin "92") (pinfunction "(ADC5/TMS)PF5_92") (pintype "bidirectional"))
      (node (ref "X40") (pin "8") (pinfunction "8_8") (pintype "passive"))
    )
    (net (code "52") (name "/PF6") (class "Default")
      (node (ref "U2") (pin "91") (pinfunction "(ADC6/TDO)PF6_91") (pintype "bidirectional"))
      (node (ref "X40") (pin "3") (pinfunction "3_3") (pintype "passive"))
    )
    (net (code "53") (name "/PG3") (class "Default")
      (node (ref "U2") (pin "28") (pinfunction "(TOSC2)PG3_28") (pintype "bidirectional"))
      (node (ref "X13") (pin "7") (pinfunction "7_7") (pintype "passive"))
    )
    (net (code "54") (name "/PG4") (class "Default")
      (node (ref "U2") (pin "29") (pinfunction "(TOSC1)PG4_29") (pintype "bidirectional"))
      (node (ref "X13") (pin "5") (pinfunction "5_5") (pintype "passive"))
    )
    (net (code "55") (name "/PG5") (class "Default")
      (node (ref "U2") (pin "1") (pinfunction "(OC0B)PG5_1") (pintype "bidirectional"))
      (node (ref "X34") (pin "6") (pinfunction "6_6") (pintype "passive"))
      (node (ref "X5") (pin "1") (pinfunction "S_1") (pintype "passive"))
    )
    (net (code "56") (name "/PH2") (class "Default")
      (node (ref "U2") (pin "14") (pinfunction "PH2(XCK2)_14") (pintype "bidirectional"))
      (node (ref "X13") (pin "8") (pinfunction "8_8") (pintype "passive"))
    )
    (net (code "57") (name "/PH7") (class "Default")
      (node (ref "U2") (pin "27") (pinfunction "PH7(T4)_27") (pintype "bidirectional"))
      (node (ref "X13") (pin "6") (pinfunction "6_6") (pintype "passive"))
    )
    (net (code "58") (name "/PJ2") (class "Default")
      (node (ref "U2") (pin "65") (pinfunction "PJ2(XCK3/PCINT11)_65") (pintype "bidirectional"))
      (node (ref "X13") (pin "9") (pinfunction "9_9") (pintype "passive"))
    )
    (net (code "59") (name "/PJ3") (class "Default")
      (node (ref "U2") (pin "66") (pinfunction "PJ3(PCINT12)_66") (pintype "bidirectional"))
      (node (ref "X13") (pin "11") (pinfunction "11_11") (pintype "passive"))
    )
    (net (code "60") (name "/PJ4") (class "Default")
      (node (ref "U2") (pin "67") (pinfunction "PJ4(PCINT13)_67") (pintype "bidirectional"))
      (node (ref "X13") (pin "15") (pinfunction "15_15") (pintype "passive"))
    )
    (net (code "61") (name "/PJ5") (class "Default")
      (node (ref "U2") (pin "68") (pinfunction "PJ5(PCINT14)_68") (pintype "bidirectional"))
      (node (ref "X13") (pin "17") (pinfunction "17_17") (pintype "passive"))
    )
    (net (code "62") (name "/PJ6") (class "Default")
      (node (ref "U2") (pin "69") (pinfunction "PJ6(PCINT15)_69") (pintype "bidirectional"))
      (node (ref "X13") (pin "19") (pinfunction "19_19") (pintype "passive"))
    )
    (net (code "63") (name "/PJ7") (class "Default")
      (node (ref "U2") (pin "79") (pinfunction "PJ7_79") (pintype "bidirectional"))
      (node (ref "X13") (pin "13") (pinfunction "13_13") (pintype "passive"))
    )
    (net (code "64") (name "/PK0") (class "Default")
      (node (ref "U2") (pin "89") (pinfunction "PK0(ADC8/PCINT16)_89") (pintype "bidirectional"))
      (node (ref "X40") (pin "7") (pinfunction "7_7") (pintype "passive"))
    )
    (net (code "65") (name "/PL3") (class "Default")
      (node (ref "U2") (pin "38") (pinfunction "PL3(OC5A)_38") (pintype "bidirectional"))
      (node (ref "X12") (pin "2") (pinfunction "2_2") (pintype "passive"))
      (node (ref "X32") (pin "5") (pinfunction "5_5") (pintype "passive"))
    )
    (net (code "66") (name "/PL4") (class "Default")
      (node (ref "U2") (pin "39") (pinfunction "PL4(OC5B)_39") (pintype "bidirectional"))
      (node (ref "X31") (pin "5") (pinfunction "5_5") (pintype "passive"))
    )
    (net (code "67") (name "/PL5") (class "Default")
      (node (ref "U2") (pin "40") (pinfunction "PL5(OC5C)_40") (pintype "bidirectional"))
      (node (ref "X20") (pin "5") (pinfunction "5_5") (pintype "passive"))
    )
    (net (code "68") (name "/RD+") (class "Default")
      (node (ref "R2") (pin "2") (pinfunction "2_2") (pintype "passive"))
      (node (ref "U1") (pin "29") (pinfunction "D+_29") (pintype "bidirectional"))
    )
    (net (code "69") (name "/RD-") (class "Default")
      (node (ref "R1") (pin "2") (pinfunction "2_2") (pintype "passive"))
      (node (ref "U1") (pin "30") (pinfunction "D-_30") (pintype "bidirectional"))
    )
    (net (code "70") (name "/RESET") (class "Default")
      (node (ref "C1") (pin "1") (pinfunction "1_1") (pintype "passive"))
      (node (ref "C10") (pin "2") (pinfunction "2_2") (pintype "passive"))
      (node (ref "D5") (pin "A") (pinfunction "A_A") (pintype "passive"))
      (node (ref "R46") (pin "1") (pinfunction "1_1") (pintype "passive"))
      (node (ref "S1") (pin "1") (pinfunction "P_1") (pintype "passive"))
      (node (ref "U2") (pin "30") (pinfunction "RESET_30") (pintype "input"))
      (node (ref "X18") (pin "5") (pinfunction "5_5") (pintype "passive"))
    )
    (net (code "71") (name "/RESET2") (class "Default")
      (node (ref "D4") (pin "A") (pinfunction "A_A") (pintype "passive"))
      (node (ref "R47") (pin "1") (pinfunction "1_1") (pintype "passive"))
      (node (ref "U1") (pin "24") (pinfunction "RESET(PC1/DW)_24") (pintype "input"))
      (node (ref "X17") (pin "5") (pinfunction "5_5") (pintype "passive"))
    )
    (net (code "72") (name "/RST-IO") (class "Default")
      (node (ref "C10") (pin "1") (pinfunction "1_1") (pintype "passive"))
      (node (ref "U10") (pin "14") (pinfunction "VOA_14") (pintype "bidirectional"))
    )
    (net (code "73") (name "/RX0") (class "Default")
      (node (ref "R34") (pin "2") (pinfunction "2_2") (pintype "passive"))
      (node (ref "U2") (pin "2") (pinfunction "(RXD0/PCIN8)PE0_2") (pintype "bidirectional"))
      (node (ref "X39") (pin "3") (pinfunction "3_3") (pintype "passive"))
    )
    (net (code "74") (name "/RX0-I") (class "Default")
      (node (ref "U1") (pin "9") (pinfunction "(TXD1/INT3)PD3_9") (pintype "bidirectional"))
      (node (ref "U10") (pin "5") (pinfunction "VIC_5") (pintype "bidirectional"))
    )
    (net (code "75") (name "/RX1") (class "Default")
      (node (ref "U2") (pin "45") (pinfunction "(RXD1/INT2)PD2_45") (pintype "bidirectional"))
      (node (ref "X39") (pin "5") (pinfunction "5_5") (pintype "passive"))
    )
    (net (code "76") (name "/RX2") (class "Default")
      (node (ref "U2") (pin "12") (pinfunction "PH0(RXD2)_12") (pintype "bidirectional"))
      (node (ref "X39") (pin "7") (pinfunction "7_7") (pintype "passive"))
    )
    (net (code "77") (name "/RX3") (class "Default")
      (node (ref "U2") (pin "63") (pinfunction "PJ0(RXD3/PCINT9)_63") (pintype "bidirectional"))
      (node (ref "X39") (pin "9") (pinfunction "9_9") (pintype "passive"))
    )
    (net (code "78") (name "/RXL") (class "Default")
      (node (ref "LED10") (pin "C") (pinfunction "C_C") (pintype "passive"))
      (node (ref "U1") (pin "10") (pinfunction "(INT5/AIN3)PD4_10") (pintype "bidirectional"))
    )
    (net (code "79") (name "/SCK2") (class "Default")
      (node (ref "U1") (pin "15") (pinfunction "(SCLK/PCINT1)PB1_15") (pintype "bidirectional"))
      (node (ref "X17") (pin "3") (pinfunction "3_3") (pintype "passive"))
    )
    (net (code "80") (name "/SCL") (class "Default")
      (node (ref "R45") (pin "1") (pinfunction "1_1") (pintype "passive"))
      (node (ref "U2") (pin "43") (pinfunction "(SCL/INT0)PD0_43") (pintype "bidirectional"))
      (node (ref "X10") (pin "4") (pinfunction "S_4") (pintype "passive"))
    )
    (net (code "81") (name "/SDA") (class "Default")
      (node (ref "R44") (pin "1") (pinfunction "1_1") (pintype "passive"))
      (node (ref "U2") (pin "44") (pinfunction "(SDA/INT1)PD1_44") (pintype "bidirectional"))
      (node (ref "X10") (pin "3") (pinfunction "S_3") (pintype "passive"))
    )
    (net (code "82") (name "/THERM0") (class "Default")
      (node (ref "C59") (pin "1") (pinfunction "1_1") (pintype "passive"))
      (node (ref "D11") (pin "A") (pinfunction "A_A") (pintype "passive"))
      (node (ref "D13") (pin "C") (pinfunction "C_C") (pintype "passive"))
      (node (ref "R32") (pin "1") (pinfunction "1_1") (pintype "passive"))
      (node (ref "TP20") (pin "TP") (pinfunction "TP_TP") (pintype "input"))
      (node (ref "U2") (pin "97") (pinfunction "(ADC0)PF0_97") (pintype "bidirectional"))
    )
    (net (code "83") (name "/THERM1") (class "Default")
      (node (ref "C56") (pin "1") (pinfunction "1_1") (pintype "passive"))
      (node (ref "D14") (pin "A") (pinfunction "A_A") (pintype "passive"))
      (node (ref "D15") (pin "C") (pinfunction "C_C") (pintype "passive"))
      (node (ref "R37") (pin "1") (pinfunction "1_1") (pintype "passive"))
      (node (ref "TP21") (pin "TP") (pinfunction "TP_TP") (pintype "input"))
      (node (ref "U2") (pin "96") (pinfunction "(ADC1)PF1_96") (pintype "bidirectional"))
    )
    (net (code "84") (name "/THERM2") (class "Default")
      (node (ref "C64") (pin "1") (pinfunction "1_1") (pintype "passive"))
      (node (ref "D16") (pin "A") (pinfunction "A_A") (pintype "passive"))
      (node (ref "D17") (pin "C") (pinfunction "C_C") (pintype "passive"))
      (node (ref "R28") (pin "1") (pinfunction "1_1") (pintype "passive"))
      (node (ref "TP22") (pin "TP") (pinfunction "TP_TP") (pintype "input"))
      (node (ref "U2") (pin "95") (pinfunction "(ADC2)PF2_95") (pintype "bidirectional"))
    )
    (net (code "85") (name "/THERM3") (class "Default")
      (node (ref "C3") (pin "1") (pinfunction "1_1") (pintype "passive"))
      (node (ref "D18") (pin "A") (pinfunction "A_A") (pintype "passive"))
      (node (ref "D19") (pin "C") (pinfunction "C_C") (pintype "passive"))
      (node (ref "R39") (pin "1") (pinfunction "1_1") (pintype "passive"))
      (node (ref "TP23") (pin "TP") (pinfunction "TP_TP") (pintype "input"))
      (node (ref "U2") (pin "90") (pinfunction "(ADC7/TDI)PF7_90") (pintype "bidirectional"))
      (node (ref "X40") (pin "5") (pinfunction "5_5") (pintype "passive"))
    )
    (net (code "86") (name "/TX0") (class "Default")
      (node (ref "U10") (pin "11") (pinfunction "VID_11") (pintype "bidirectional"))
      (node (ref "U2") (pin "3") (pinfunction "(TXD0)PE1_3") (pintype "bidirectional"))
      (node (ref "X39") (pin "4") (pinfunction "4_4") (pintype "passive"))
    )
    (net (code "87") (name "/TX0-I") (class "Default")
      (node (ref "U1") (pin "8") (pinfunction "(RXD1/AIN1/INT2)PD2_8") (pintype "bidirectional"))
      (node (ref "U10") (pin "6") (pinfunction "VOD_6") (pintype "bidirectional"))
    )
    (net (code "88") (name "/TX1") (class "Default")
      (node (ref "U2") (pin "46") (pinfunction "(TXD1/INT3)PD3_46") (pintype "bidirectional"))
      (node (ref "X39") (pin "6") (pinfunction "6_6") (pintype "passive"))
    )
    (net (code "89") (name "/TX2") (class "Default")
      (node (ref "U2") (pin "13") (pinfunction "PH1(TXD2)_13") (pintype "bidirectional"))
      (node (ref "X39") (pin "8") (pinfunction "8_8") (pintype "passive"))
    )
    (net (code "90") (name "/TX3") (class "Default")
      (node (ref "U2") (pin "64") (pinfunction "PJ1(TXD3/PCINT10)_64") (pintype "bidirectional"))
      (node (ref "X39") (pin "10") (pinfunction "10_10") (pintype "passive"))
    )
    (net (code "91") (name "/TXL") (class "Default")
      (node (ref "LED9") (pin "C") (pinfunction "C_C") (pintype "passive"))
      (node (ref "U1") (pin "11") (pinfunction "(XCK/AIN4/PCINT12)PD5_11") (pintype "bidirectional"))
    )
    (net (code "92") (name "/U1-PB0") (class "Default")
      (node (ref "U1") (pin "14") (pinfunction "(SS/PCINT0)PB0_14") (pintype "bidirectional"))
      (node (ref "X16") (pin "7") (pinfunction "7_7") (pintype "passive"))
    )
    (net (code "93") (name "/U1-PB4") (class "Default")
      (node (ref "U1") (pin "18") (pinfunction "(T1/PCINT4)PB4_18") (pintype "bidirectional"))
      (node (ref "X16") (pin "9") (pinfunction "9_9") (pintype "passive"))
    )
    (net (code "94") (name "/U1-PB5") (class "Default")
      (node (ref "U1") (pin "19") (pinfunction "(PCINT5)PB5_19") (pintype "bidirectional"))
      (node (ref "X16") (pin "12") (pinfunction "12_12") (pintype "passive"))
    )
    (net (code "95") (name "/U1-PB6") (class "Default")
      (node (ref "U1") (pin "20") (pinfunction "(PCINT6)PB6_20") (pintype "bidirectional"))
      (node (ref "X16") (pin "11") (pinfunction "11_11") (pintype "passive"))
    )
    (net (code "96") (name "/U1-PB7") (class "Default")
      (node (ref "U1") (pin "21") (pinfunction "(PCINT7/OC0A/OC1C)PB7_21") (pintype "bidirectional"))
      (node (ref "X16") (pin "14") (pinfunction "14_14") (pintype "passive"))
    )
    (net (code "97") (name "/U1-PC2") (class "Default")
      (node (ref "U1") (pin "5") (pinfunction "(AIN2/PCINT11)PC2_5") (pintype "bidirectional"))
      (node (ref "X16") (pin "5") (pinfunction "5_5") (pintype "passive"))
    )
    (net (code "98") (name "/U1-PC4") (class "Default")
      (node (ref "U1") (pin "26") (pinfunction "(PCINT10)PC4_26") (pintype "bidirectional"))
    )
    (net (code "99") (name "/U1-PC5") (class "Default")
      (node (ref "U1") (pin "25") (pinfunction "(PCINT9/OC1B)PC5_25") (pintype "bidirectional"))
      (node (ref "X16") (pin "15") (pinfunction "15_15") (pintype "passive"))
    )
    (net (code "100") (name "/U1-PC6") (class "Default")
      (node (ref "U1") (pin "23") (pinfunction "(OC1A/PCINT8)PC6_23") (pintype "bidirectional"))
      (node (ref "X16") (pin "16") (pinfunction "16_16") (pintype "passive"))
    )
    (net (code "101") (name "/U1-PC7") (class "Default")
      (node (ref "U1") (pin "22") (pinfunction "(INT4/ICP1/CLK0)PC7_22") (pintype "bidirectional"))
      (node (ref "X16") (pin "13") (pinfunction "13_13") (pintype "passive"))
    )
    (net (code "102") (name "/U1-PD0") (class "Default")
      (node (ref "U1") (pin "6") (pinfunction "(OC0B/INT0)PD0_6") (pintype "bidirectional"))
      (node (ref "X16") (pin "10") (pinfunction "10_10") (pintype "passive"))
    )
    (net (code "103") (name "/U1-PD1") (class "Default")
      (node (ref "U1") (pin "7") (pinfunction "(AIN0/INT1)PD1_7") (pintype "bidirectional"))
      (node (ref "X16") (pin "8") (pinfunction "8_8") (pintype "passive"))
    )
    (net (code "104") (name "/U1-PD6") (class "Default")
      (node (ref "U1") (pin "12") (pinfunction "(RTS/AIN5/INT6)PD6_12") (pintype "bidirectional"))
      (node (ref "X16") (pin "6") (pinfunction "6_6") (pintype "passive"))
    )
    (net (code "105") (name "/USBVCC") (class "Default")
      (node (ref "C11") (pin "1") (pinfunction "1_1") (pintype "passive"))
      (node (ref "C14") (pin "1") (pinfunction "1_1") (pintype "passive"))
      (node (ref "C15") (pin "1") (pinfunction "1_1") (pintype "passive"))
      (node (ref "C19") (pin "1") (pinfunction "1_1") (pintype "passive"))
      (node (ref "C2") (pin "2") (pinfunction "2_2") (pintype "passive"))
      (node (ref "C5") (pin "1") (pinfunction "1_1") (pintype "passive"))
      (node (ref "D4") (pin "C") (pinfunction "C_C") (pintype "passive"))
      (node (ref "F1") (pin "1") (pinfunction "1_1") (pintype "passive"))
      (node (ref "R47") (pin "2") (pinfunction "2_2") (pintype "passive"))
      (node (ref "RN5") (pin "2") (pinfunction "1_2") (pintype "passive"))
      (node (ref "RN5") (pin "3") (pinfunction "1_3") (pintype "passive"))
      (node (ref "RN5") (pin "4") (pinfunction "1_4") (pintype "passive"))
      (node (ref "U1") (pin "31") (pinfunction "UVCC_31") (pintype "power_in"))
      (node (ref "U1") (pin "32") (pinfunction "AVCC_32") (pintype "power_in"))
      (node (ref "U1") (pin "4") (pinfunction "VCC_4") (pintype "power_in"))
      (node (ref "U10") (pin "1") (pinfunction "VDD1A_1") (pintype "bidirectional"))
      (node (ref "U10") (pin "7") (pinfunction "VDD1B_7") (pintype "bidirectional"))
      (node (ref "X16") (pin "1") (pinfunction "1_1") (pintype "passive"))
      (node (ref "X16") (pin "2") (pinfunction "2_2") (pintype "passive"))
      (node (ref "X17") (pin "2") (pinfunction "2_2") (pintype "passive"))
    )
    (net (code "106") (name "/USHIELD") (class "Default")
      (node (ref "C63") (pin "1") (pinfunction "1_1") (pintype "passive"))
      (node (ref "R72") (pin "2") (pinfunction "2_2") (pintype "passive"))
      (node (ref "X2") (pin "P$1") (pinfunction "P$1_P$1") (pintype "bidirectional"))
      (node (ref "X2") (pin "P$2") (pinfunction "P$2_P$2") (pintype "bidirectional"))
      (node (ref "Z1") (pin "1") (pinfunction "1_1") (pintype "passive"))
      (node (ref "Z2") (pin "1") (pinfunction "1_1") (pintype "passive"))
    )
    (net (code "107") (name "/VUCAP") (class "Default")
      (node (ref "C16") (pin "1") (pinfunction "1_1") (pintype "passive"))
      (node (ref "U1") (pin "27") (pinfunction "UCAP_27") (pintype "passive"))
    )
    (net (code "108") (name "/X-DIR") (class "Default")
      (node (ref "TP1") (pin "TP") (pinfunction "TP_TP") (pintype "input"))
      (node (ref "U2") (pin "36") (pinfunction "PL1(ICP5)_36") (pintype "bidirectional"))
      (node (ref "U5") (pin "20") (pinfunction "DIR_20") (pintype "input"))
    )
    (net (code "109") (name "/X-EN") (class "Default")
      (node (ref "R60") (pin "2") (pinfunction "2_2") (pintype "passive"))
      (node (ref "TP4") (pin "TP") (pinfunction "TP_TP") (pintype "input"))
      (node (ref "U2") (pin "71") (pinfunction "(AD7)PA7_71") (pintype "bidirectional"))
      (node (ref "U5") (pin "5") (pinfunction "EN_5") (pintype "input"))
    )
    (net (code "110") (name "/X-MIN") (class "Default")
      (node (ref "U2") (pin "25") (pinfunction "(OC1B/PCINT6)PB6_25") (pintype "bidirectional"))
      (node (ref "X23") (pin "1") (pinfunction "S_1") (pintype "passive"))
    )
    (net (code "111") (name "/X-MS1") (class "Default")
      (node (ref "U2") (pin "52") (pinfunction "(RD)PG1_52") (pintype "bidirectional"))
      (node (ref "U5") (pin "11") (pinfunction "MS1_11") (pintype "input"))
    )
    (net (code "112") (name "/X-MS2") (class "Default")
      (node (ref "U2") (pin "51") (pinfunction "(WR)PG0_51") (pintype "bidirectional"))
      (node (ref "U5") (pin "12") (pinfunction "MS2_12") (pintype "input"))
    )
    (net (code "113") (name "/X-REF") (class "Default")
      (node (ref "TP3") (pin "TP") (pinfunction "TP_TP") (pintype "input"))
      (node (ref "U4") (pin "P11") (pinfunction "W5_P11") (pintype "bidirectional"))
      (node (ref "U5") (pin "18") (pinfunction "REF_18") (pintype "input"))
    )
    (net (code "114") (name "/X-STEP") (class "Default")
      (node (ref "TP2") (pin "TP") (pinfunction "TP_TP") (pintype "input"))
      (node (ref "U2") (pin "53") (pinfunction "(A8)PC0_53") (pintype "bidirectional"))
      (node (ref "U5") (pin "17") (pinfunction "STEP_17") (pintype "input"))
    )
    (net (code "115") (name "/XVCC") (class "Default")
      (node (ref "F1") (pin "2") (pinfunction "2_2") (pintype "passive"))
      (node (ref "X2") (pin "1") (pinfunction "1_1") (pintype "bidirectional"))
    )
    (net (code "116") (name "/Y-DIR") (class "Default")
      (node (ref "TP0") (pin "TP") (pinfunction "TP_TP") (pintype "input"))
      (node (ref "U2") (pin "35") (pinfunction "PL0(ICP4)_35") (pintype "bidirectional"))
      (node (ref "U6") (pin "20") (pinfunction "DIR_20") (pintype "input"))
    )
    (net (code "117") (name "/Y-EN") (class "Default")
      (node (ref "R59") (pin "2") (pinfunction "2_2") (pintype "passive"))
      (node (ref "TP7") (pin "TP") (pinfunction "TP_TP") (pintype "input"))
      (node (ref "U2") (pin "72") (pinfunction "(AD6)PA6_72") (pintype "bidirectional"))
      (node (ref "U6") (pin "5") (pinfunction "EN_5") (pintype "input"))
    )
    (net (code "118") (name "/Y-MIN") (class "Default")
      (node (ref "U2") (pin "24") (pinfunction "(OC1A/PCINT5)PB5_24") (pintype "bidirectional"))
      (node (ref "X22") (pin "1") (pinfunction "S_1") (pintype "passive"))
    )
    (net (code "119") (name "/Y-MS1") (class "Default")
      (node (ref "U2") (pin "82") (pinfunction "PK7(ADC15/PCINT23)_82") (pintype "bidirectional"))
      (node (ref "U6") (pin "11") (pinfunction "MS1_11") (pintype "input"))
    )
    (net (code "120") (name "/Y-MS2") (class "Default")
      (node (ref "U2") (pin "70") (pinfunction "(ALE)PG2_70") (pintype "bidirectional"))
      (node (ref "U6") (pin "12") (pinfunction "MS2_12") (pintype "input"))
    )
    (net (code "121") (name "/Y-REF") (class "Default")
      (node (ref "TP6") (pin "TP") (pinfunction "TP_TP") (pintype "input"))
      (node (ref "U4") (pin "P02") (pinfunction "W6_P02") (pintype "bidirectional"))
      (node (ref "U6") (pin "18") (pinfunction "REF_18") (pintype "input"))
    )
    (net (code "122") (name "/Y-STEP") (class "Default")
      (node (ref "TP5") (pin "TP") (pinfunction "TP_TP") (pintype "input"))
      (node (ref "U2") (pin "54") (pinfunction "(A9)PC1_54") (pintype "bidirectional"))
      (node (ref "U6") (pin "17") (pinfunction "STEP_17") (pintype "input"))
    )
    (net (code "123") (name "/Z-DIR") (class "Default")
      (node (ref "TP19") (pin "TP") (pinfunction "TP_TP") (pintype "input"))
      (node (ref "U2") (pin "37") (pinfunction "PL2(T5)_37") (pintype "bidirectional"))
      (node (ref "U7") (pin "20") (pinfunction "DIR_20") (pintype "input"))
    )
    (net (code "124") (name "/Z-EN") (class "Default")
      (node (ref "R61") (pin "2") (pinfunction "2_2") (pintype "passive"))
      (node (ref "TP10") (pin "TP") (pinfunction "TP_TP") (pintype "input"))
      (node (ref "U2") (pin "73") (pinfunction "(AD5)PA5_73") (pintype "bidirectional"))
      (node (ref "U7") (pin "5") (pinfunction "EN_5") (pintype "input"))
    )
    (net (code "125") (name "/Z-MIN") (class "Default")
      (node (ref "U2") (pin "23") (pinfunction "(OC2A/PCINT4)PB4_23") (pintype "bidirectional"))
      (node (ref "X21") (pin "1") (pinfunction "S_1") (pintype "passive"))
    )
    (net (code "126") (name "/Z-MS1") (class "Default")
      (node (ref "U2") (pin "83") (pinfunction "PK6(ADC14/PCINT22)_83") (pintype "bidirectional"))
      (node (ref "U7") (pin "11") (pinfunction "MS1_11") (pintype "input"))
    )
    (net (code "127") (name "/Z-MS2") (class "Default")
      (node (ref "U2") (pin "84") (pinfunction "PK5(ADC13/PCINT21)_84") (pintype "bidirectional"))
      (node (ref "U7") (pin "12") (pinfunction "MS2_12") (pintype "input"))
    )
    (net (code "128") (name "/Z-REF") (class "Default")
      (node (ref "TP9") (pin "TP") (pinfunction "TP_TP") (pintype "input"))
      (node (ref "U4") (pin "P23") (pinfunction "W4_P23") (pintype "bidirectional"))
      (node (ref "U7") (pin "18") (pinfunction "REF_18") (pintype "input"))
    )
    (net (code "129") (name "/Z-STEP") (class "Default")
      (node (ref "TP8") (pin "TP") (pinfunction "TP_TP") (pintype "input"))
      (node (ref "U2") (pin "55") (pinfunction "(A10)PC2_55") (pintype "bidirectional"))
      (node (ref "U7") (pin "17") (pinfunction "STEP_17") (pintype "input"))
    )
    (net (code "130") (name "GND") (class "Default")
      (node (ref "C1") (pin "2") (pinfunction "2_2") (pintype "passive"))
      (node (ref "C17") (pin "2") (pinfunction "2_2") (pintype "passive"))
      (node (ref "C18") (pin "2") (pinfunction "2_2") (pintype "passive"))
      (node (ref "C20") (pin "2") (pinfunction "2_2") (pintype "passive"))
      (node (ref "C21") (pin "1") (pinfunction "1_1") (pintype "passive"))
      (node (ref "C23") (pin "2") (pinfunction "2_2") (pintype "passive"))
      (node (ref "C24") (pin "2") (pinfunction "2_2") (pintype "passive"))
      (node (ref "C25") (pin "2") (pinfunction "2_2") (pintype "passive"))
      (node (ref "C26") (pin "2") (pinfunction "2_2") (pintype "passive"))
      (node (ref "C29") (pin "2") (pinfunction "2_2") (pintype "passive"))
      (node (ref "C3") (pin "2") (pinfunction "2_2") (pintype "passive"))
      (node (ref "C30") (pin "2") (pinfunction "2_2") (pintype "passive"))
      (node (ref "C31") (pin "1") (pinfunction "1_1") (pintype "passive"))
      (node (ref "C34") (pin "2") (pinfunction "2_2") (pintype "passive"))
      (node (ref "C36") (pin "1") (pinfunction "1_1") (pintype "passive"))
      (node (ref "C39") (pin "2") (pinfunction "2_2") (pintype "passive"))
      (node (ref "C4") (pin "2") (pinfunction "2_2") (pintype "passive"))
      (node (ref "C40") (pin "2") (pinfunction "2_2") (pintype "passive"))
      (node (ref "C41") (pin "1") (pinfunction "1_1") (pintype "passive"))
      (node (ref "C44") (pin "2") (pinfunction "2_2") (pintype "passive"))
      (node (ref "C45") (pin "2") (pinfunction "2_2") (pintype "passive"))
      (node (ref "C46") (pin "1") (pinfunction "1_1") (pintype "passive"))
      (node (ref "C49") (pin "2") (pinfunction "2_2") (pintype "passive"))
      (node (ref "C51") (pin "1") (pinfunction "1_1") (pintype "passive"))
      (node (ref "C52") (pin "2") (pinfunction "2_2") (pintype "passive"))
      (node (ref "C53") (pin "2") (pinfunction "2_2") (pintype "passive"))
      (node (ref "C54") (pin "2") (pinfunction "2_2") (pintype "passive"))
      (node (ref "C55") (pin "2") (pinfunction "2_2") (pintype "passive"))
      (node (ref "C56") (pin "2") (pinfunction "2_2") (pintype "passive"))
      (node (ref "C57") (pin "2") (pinfunction "2_2") (pintype "passive"))
      (node (ref "C58") (pin "2") (pinfunction "2_2") (pintype "passive"))
      (node (ref "C59") (pin "2") (pinfunction "2_2") (pintype "passive"))
      (node (ref "C6") (pin "2") (pinfunction "2_2") (pintype "passive"))
      (node (ref "C60") (pin "2") (pinfunction "2_2") (pintype "passive"))
      (node (ref "C62") (pin "2") (pinfunction "2_2") (pintype "passive"))
      (node (ref "C64") (pin "2") (pinfunction "2_2") (pintype "passive"))
      (node (ref "C65") (pin "-") (pinfunction "-_-") (pintype "passive"))
      (node (ref "C66") (pin "-") (pinfunction "-_-") (pintype "passive"))
      (node (ref "C7") (pin "2") (pinfunction "2_2") (pintype "passive"))
      (node (ref "C71") (pin "2") (pinfunction "2_2") (pintype "passive"))
      (node (ref "C72") (pin "2") (pinfunction "2_2") (pintype "passive"))
      (node (ref "C73") (pin "2") (pinfunction "2_2") (pintype "passive"))
      (node (ref "C74") (pin "2") (pinfunction "2_2") (pintype "passive"))
      (node (ref "C75") (pin "2") (pinfunction "2_2") (pintype "passive"))
      (node (ref "C76") (pin "-") (pinfunction "-_-") (pintype "passive"))
      (node (ref "C8") (pin "2") (pinfunction "2_2") (pintype "passive"))
      (node (ref "C9") (pin "2") (pinfunction "2_2") (pintype "passive"))
      (node (ref "CF1") (pin "2@1") (pinfunction "2_2@1") (pintype "passive"))
      (node (ref "CF1") (pin "2@2") (pinfunction "2_2@2") (pintype "passive"))
      (node (ref "CF10") (pin "2@1") (pinfunction "2_2@1") (pintype "passive"))
      (node (ref "CF10") (pin "2@2") (pinfunction "2_2@2") (pintype "passive"))
      (node (ref "CF11") (pin "2@1") (pinfunction "2_2@1") (pintype "passive"))
      (node (ref "CF11") (pin "2@2") (pinfunction "2_2@2") (pintype "passive"))
      (node (ref "CF12") (pin "2@1") (pinfunction "2_2@1") (pintype "passive"))
      (node (ref "CF12") (pin "2@2") (pinfunction "2_2@2") (pintype "passive"))
      (node (ref "CF13") (pin "2@1") (pinfunction "2_2@1") (pintype "passive"))
      (node (ref "CF13") (pin "2@2") (pinfunction "2_2@2") (pintype "passive"))
      (node (ref "CF14") (pin "2@1") (pinfunction "2_2@1") (pintype "passive"))
      (node (ref "CF14") (pin "2@2") (pinfunction "2_2@2") (pintype "passive"))
      (node (ref "CF15") (pin "2@1") (pinfunction "2_2@1") (pintype "passive"))
      (node (ref "CF15") (pin "2@2") (pinfunction "2_2@2") (pintype "passive"))
      (node (ref "CF16") (pin "2@1") (pinfunction "2_2@1") (pintype "passive"))
      (node (ref "CF16") (pin "2@2") (pinfunction "2_2@2") (pintype "passive"))
      (node (ref "CF17") (pin "2@1") (pinfunction "2_2@1") (pintype "passive"))
      (node (ref "CF17") (pin "2@2") (pinfunction "2_2@2") (pintype "passive"))
      (node (ref "CF18") (pin "2@1") (pinfunction "2_2@1") (pintype "passive"))
      (node (ref "CF18") (pin "2@2") (pinfunction "2_2@2") (pintype "passive"))
      (node (ref "CF19") (pin "2@1") (pinfunction "2_2@1") (pintype "passive"))
      (node (ref "CF19") (pin "2@2") (pinfunction "2_2@2") (pintype "passive"))
      (node (ref "CF2") (pin "2@1") (pinfunction "2_2@1") (pintype "passive"))
      (node (ref "CF2") (pin "2@2") (pinfunction "2_2@2") (pintype "passive"))
      (node (ref "CF20") (pin "2@1") (pinfunction "2_2@1") (pintype "passive"))
      (node (ref "CF20") (pin "2@2") (pinfunction "2_2@2") (pintype "passive"))
      (node (ref "CF3") (pin "2@1") (pinfunction "2_2@1") (pintype "passive"))
      (node (ref "CF3") (pin "2@2") (pinfunction "2_2@2") (pintype "passive"))
      (node (ref "CF4") (pin "2@1") (pinfunction "2_2@1") (pintype "passive"))
      (node (ref "CF4") (pin "2@2") (pinfunction "2_2@2") (pintype "passive"))
      (node (ref "CF5") (pin "2@1") (pinfunction "2_2@1") (pintype "passive"))
      (node (ref "CF5") (pin "2@2") (pinfunction "2_2@2") (pintype "passive"))
      (node (ref "CF6") (pin "2@1") (pinfunction "2_2@1") (pintype "passive"))
      (node (ref "CF6") (pin "2@2") (pinfunction "2_2@2") (pintype "passive"))
      (node (ref "CF7") (pin "2@1") (pinfunction "2_2@1") (pintype "passive"))
      (node (ref "CF7") (pin "2@2") (pinfunction "2_2@2") (pintype "passive"))
      (node (ref "CF8") (pin "2@1") (pinfunction "2_2@1") (pintype "passive"))
      (node (ref "CF8") (pin "2@2") (pinfunction "2_2@2") (pintype "passive"))
      (node (ref "CF9") (pin "2@1") (pinfunction "2_2@1") (pintype "passive"))
      (node (ref "CF9") (pin "2@2") (pinfunction "2_2@2") (pintype "passive"))
      (node (ref "D12") (pin "A") (pinfunction "A_A") (pintype "passive"))
      (node (ref "D13") (pin "A") (pinfunction "A_A") (pintype "passive"))
      (node (ref "D15") (pin "A") (pinfunction "A_A") (pintype "passive"))
      (node (ref "D17") (pin "A") (pinfunction "A_A") (pintype "passive"))
      (node (ref "D19") (pin "A") (pinfunction "A_A") (pintype "passive"))
      (node (ref "D2") (pin "A") (pinfunction "A_A") (pintype "passive"))
      (node (ref "D20") (pin "A") (pinfunction "A_A") (pintype "passive"))
      (node (ref "D21") (pin "A") (pinfunction "A_A") (pintype "passive"))
      (node (ref "D22") (pin "A") (pinfunction "A_A") (pintype "passive"))
      (node (ref "D23") (pin "A") (pinfunction "A_A") (pintype "passive"))
      (node (ref "D24") (pin "A") (pinfunction "A_A") (pintype "passive"))
      (node (ref "D25") (pin "A") (pinfunction "A_A") (pintype "passive"))
      (node (ref "D26") (pin "A") (pinfunction "A_A") (pintype "passive"))
      (node (ref "D27") (pin "A") (pinfunction "A_A") (pintype "passive"))
      (node (ref "D28") (pin "A") (pinfunction "A_A") (pintype "passive"))
      (node (ref "D29") (pin "A") (pinfunction "A_A") (pintype "passive"))
      (node (ref "D30") (pin "A") (pinfunction "A_A") (pintype "passive"))
      (node (ref "D31") (pin "A") (pinfunction "A_A") (pintype "passive"))
      (node (ref "D32") (pin "A") (pinfunction "A_A") (pintype "passive"))
      (node (ref "D33") (pin "A") (pinfunction "A_A") (pintype "passive"))
      (node (ref "D34") (pin "A") (pinfunction "A_A") (pintype "passive"))
      (node (ref "D35") (pin "A") (pinfunction "A_A") (pintype "passive"))
      (node (ref "D36") (pin "A") (pinfunction "A_A") (pintype "passive"))
      (node (ref "D37") (pin "A") (pinfunction "A_A") (pintype "passive"))
      (node (ref "D38") (pin "A") (pinfunction "A_A") (pintype "passive"))
      (node (ref "D39") (pin "A") (pinfunction "A_A") (pintype "passive"))
      (node (ref "D40") (pin "C") (pinfunction "2_C") (pintype "passive"))
      (node (ref "D7") (pin "A") (pinfunction "A_A") (pintype "passive"))
      (node (ref "D8") (pin "A") (pinfunction "A_A") (pintype "passive"))
      (node (ref "D9") (pin "A") (pinfunction "A_A") (pintype "passive"))
      (node (ref "H1") (pin "P$1") (pinfunction "P$1_P$1") (pintype "bidirectional"))
      (node (ref "H1") (pin "P$17") (pinfunction "P$1_P$17") (pintype "bidirectional"))
      (node (ref "H1") (pin "P$18") (pinfunction "P$1_P$18") (pintype "bidirectional"))
      (node (ref "H1") (pin "P$19") (pinfunction "P$1_P$19") (pintype "bidirectional"))
      (node (ref "H1") (pin "P$2") (pinfunction "P$1_P$2") (pintype "bidirectional"))
      (node (ref "H1") (pin "P$20") (pinfunction "P$1_P$20") (pintype "bidirectional"))
      (node (ref "H1") (pin "P$21") (pinfunction "P$1_P$21") (pintype "bidirectional"))
      (node (ref "H1") (pin "P$22") (pinfunction "P$1_P$22") (pintype "bidirectional"))
      (node (ref "H1") (pin "P$23") (pinfunction "P$1_P$23") (pintype "bidirectional"))
      (node (ref "H1") (pin "P$24") (pinfunction "P$1_P$24") (pintype "bidirectional"))
      (node (ref "H1") (pin "P$3") (pinfunction "P$1_P$3") (pintype "bidirectional"))
      (node (ref "H1") (pin "P$4") (pinfunction "P$1_P$4") (pintype "bidirectional"))
      (node (ref "H1") (pin "P$5") (pinfunction "P$1_P$5") (pintype "bidirectional"))
      (node (ref "H1") (pin "P$6") (pinfunction "P$1_P$6") (pintype "bidirectional"))
      (node (ref "H1") (pin "P$7") (pinfunction "P$1_P$7") (pintype "bidirectional"))
      (node (ref "H1") (pin "P$8") (pinfunction "P$1_P$8") (pintype "bidirectional"))
      (node (ref "H2") (pin "P$1") (pinfunction "P$1_P$1") (pintype "bidirectional"))
      (node (ref "H2") (pin "P$17") (pinfunction "P$1_P$17") (pintype "bidirectional"))
      (node (ref "H2") (pin "P$18") (pinfunction "P$1_P$18") (pintype "bidirectional"))
      (node (ref "H2") (pin "P$19") (pinfunction "P$1_P$19") (pintype "bidirectional"))
      (node (ref "H2") (pin "P$2") (pinfunction "P$1_P$2") (pintype "bidirectional"))
      (node (ref "H2") (pin "P$20") (pinfunction "P$1_P$20") (pintype "bidirectional"))
      (node (ref "H2") (pin "P$21") (pinfunction "P$1_P$21") (pintype "bidirectional"))
      (node (ref "H2") (pin "P$22") (pinfunction "P$1_P$22") (pintype "bidirectional"))
      (node (ref "H2") (pin "P$23") (pinfunction "P$1_P$23") (pintype "bidirectional"))
      (node (ref "H2") (pin "P$24") (pinfunction "P$1_P$24") (pintype "bidirectional"))
      (node (ref "H2") (pin "P$3") (pinfunction "P$1_P$3") (pintype "bidirectional"))
      (node (ref "H2") (pin "P$4") (pinfunction "P$1_P$4") (pintype "bidirectional"))
      (node (ref "H2") (pin "P$5") (pinfunction "P$1_P$5") (pintype "bidirectional"))
      (node (ref "H2") (pin "P$6") (pinfunction "P$1_P$6") (pintype "bidirectional"))
      (node (ref "H2") (pin "P$7") (pinfunction "P$1_P$7") (pintype "bidirectional"))
      (node (ref "H2") (pin "P$8") (pinfunction "P$1_P$8") (pintype "bidirectional"))
      (node (ref "H3") (pin "P$1") (pinfunction "P$1_P$1") (pintype "bidirectional"))
      (node (ref "H3") (pin "P$17") (pinfunction "P$1_P$17") (pintype "bidirectional"))
      (node (ref "H3") (pin "P$18") (pinfunction "P$1_P$18") (pintype "bidirectional"))
      (node (ref "H3") (pin "P$19") (pinfunction "P$1_P$19") (pintype "bidirectional"))
      (node (ref "H3") (pin "P$2") (pinfunction "P$1_P$2") (pintype "bidirectional"))
      (node (ref "H3") (pin "P$20") (pinfunction "P$1_P$20") (pintype "bidirectional"))
      (node (ref "H3") (pin "P$21") (pinfunction "P$1_P$21") (pintype "bidirectional"))
      (node (ref "H3") (pin "P$22") (pinfunction "P$1_P$22") (pintype "bidirectional"))
      (node (ref "H3") (pin "P$23") (pinfunction "P$1_P$23") (pintype "bidirectional"))
      (node (ref "H3") (pin "P$24") (pinfunction "P$1_P$24") (pintype "bidirectional"))
      (node (ref "H3") (pin "P$3") (pinfunction "P$1_P$3") (pintype "bidirectional"))
      (node (ref "H3") (pin "P$4") (pinfunction "P$1_P$4") (pintype "bidirectional"))
      (node (ref "H3") (pin "P$5") (pinfunction "P$1_P$5") (pintype "bidirectional"))
      (node (ref "H3") (pin "P$6") (pinfunction "P$1_P$6") (pintype "bidirectional"))
      (node (ref "H3") (pin "P$7") (pinfunction "P$1_P$7") (pintype "bidirectional"))
      (node (ref "H3") (pin "P$8") (pinfunction "P$1_P$8") (pintype "bidirectional"))
      (node (ref "H4") (pin "P$1") (pinfunction "P$1_P$1") (pintype "bidirectional"))
      (node (ref "H4") (pin "P$17") (pinfunction "P$1_P$17") (pintype "bidirectional"))
      (node (ref "H4") (pin "P$18") (pinfunction "P$1_P$18") (pintype "bidirectional"))
      (node (ref "H4") (pin "P$19") (pinfunction "P$1_P$19") (pintype "bidirectional"))
      (node (ref "H4") (pin "P$2") (pinfunction "P$1_P$2") (pintype "bidirectional"))
      (node (ref "H4") (pin "P$20") (pinfunction "P$1_P$20") (pintype "bidirectional"))
      (node (ref "H4") (pin "P$21") (pinfunction "P$1_P$21") (pintype "bidirectional"))
      (node (ref "H4") (pin "P$22") (pinfunction "P$1_P$22") (pintype "bidirectional"))
      (node (ref "H4") (pin "P$23") (pinfunction "P$1_P$23") (pintype "bidirectional"))
      (node (ref "H4") (pin "P$24") (pinfunction "P$1_P$24") (pintype "bidirectional"))
      (node (ref "H4") (pin "P$3") (pinfunction "P$1_P$3") (pintype "bidirectional"))
      (node (ref "H4") (pin "P$4") (pinfunction "P$1_P$4") (pintype "bidirectional"))
      (node (ref "H4") (pin "P$5") (pinfunction "P$1_P$5") (pintype "bidirectional"))
      (node (ref "H4") (pin "P$6") (pinfunction "P$1_P$6") (pintype "bidirectional"))
      (node (ref "H4") (pin "P$7") (pinfunction "P$1_P$7") (pintype "bidirectional"))
      (node (ref "H4") (pin "P$8") (pinfunction "P$1_P$8") (pintype "bidirectional"))
      (node (ref "JP3") (pin "1") (pinfunction "1_1") (pintype "passive"))
      (node (ref "LED1") (pin "C") (pinfunction "C_C") (pintype "passive"))
      (node (ref "LED7") (pin "C") (pinfunction "C_C") (pintype "passive"))
      (node (ref "Q1") (pin "1") (pinfunction "S_1") (pintype "passive"))
      (node (ref "Q1") (pin "2") (pinfunction "S_2") (pintype "passive"))
      (node (ref "Q1") (pin "3") (pinfunction "S_3") (pintype "passive"))
      (node (ref "Q2") (pin "1") (pinfunction "S_1") (pintype "passive"))
      (node (ref "Q2") (pin "2") (pinfunction "S_2") (pintype "passive"))
      (node (ref "Q2") (pin "3") (pinfunction "S_3") (pintype "passive"))
      (node (ref "Q3") (pin "1") (pinfunction "S_1") (pintype "passive"))
      (node (ref "Q3") (pin "2") (pinfunction "S_2") (pintype "passive"))
      (node (ref "Q3") (pin "3") (pinfunction "S_3") (pintype "passive"))
      (node (ref "Q4") (pin "2") (pinfunction "S_2") (pintype "passive"))
      (node (ref "Q5") (pin "1") (pinfunction "S_1") (pintype "passive"))
      (node (ref "Q5") (pin "2") (pinfunction "S_2") (pintype "passive"))
      (node (ref "Q5") (pin "3") (pinfunction "S_3") (pintype "passive"))
      (node (ref "Q8") (pin "2") (pinfunction "S_2") (pintype "passive"))
      (node (ref "R10") (pin "2") (pinfunction "2_2") (pintype "passive"))
      (node (ref "R11") (pin "2") (pinfunction "2_2") (pintype "passive"))
      (node (ref "R12") (pin "1") (pinfunction "1_1") (pintype "passive"))
      (node (ref "R14") (pin "2") (pinfunction "2_2") (pintype "passive"))
      (node (ref "R15") (pin "2") (pinfunction "2_2") (pintype "passive"))
      (node (ref "R17") (pin "1") (pinfunction "1_1") (pintype "passive"))
      (node (ref "R18") (pin "1") (pinfunction "1_1") (pintype "passive"))
      (node (ref "R19") (pin "2") (pinfunction "2_2") (pintype "passive"))
      (node (ref "R20") (pin "2") (pinfunction "2_2") (pintype "passive"))
      (node (ref "R22") (pin "1") (pinfunction "1_1") (pintype "passive"))
      (node (ref "R23") (pin "2") (pinfunction "2_2") (pintype "passive"))
      (node (ref "R24") (pin "2") (pinfunction "2_2") (pintype "passive"))
      (node (ref "R26") (pin "1") (pinfunction "1_1") (pintype "passive"))
      (node (ref "R4") (pin "2") (pinfunction "2_2") (pintype "passive"))
      (node (ref "R43") (pin "2") (pinfunction "2_2") (pintype "passive"))
      (node (ref "R49") (pin "2") (pinfunction "2_2") (pintype "passive"))
      (node (ref "R52") (pin "2") (pinfunction "2_2") (pintype "passive"))
      (node (ref "R54") (pin "2") (pinfunction "2_2") (pintype "passive"))
      (node (ref "R57") (pin "2") (pinfunction "2_2") (pintype "passive"))
      (node (ref "R7") (pin "2") (pinfunction "2_2") (pintype "passive"))
      (node (ref "R71") (pin "2") (pinfunction "2_2") (pintype "passive"))
      (node (ref "R8") (pin "2") (pinfunction "2_2") (pintype "passive"))
      (node (ref "S1") (pin "2") (pinfunction "S_2") (pintype "passive"))
      (node (ref "TP24") (pin "1") (pinfunction "1_1") (pintype "passive"))
      (node (ref "U10") (pin "15") (pinfunction "GND2A_15") (pintype "bidirectional"))
      (node (ref "U10") (pin "9") (pinfunction "GND2B_9") (pintype "bidirectional"))
      (node (ref "U2") (pin "11") (pinfunction "GND_11") (pintype "power_in"))
      (node (ref "U2") (pin "32") (pinfunction "GND1_32") (pintype "power_in"))
      (node (ref "U2") (pin "62") (pinfunction "GND2_62") (pintype "power_in"))
      (node (ref "U2") (pin "81") (pinfunction "GND3_81") (pintype "power_in"))
      (node (ref "U2") (pin "99") (pinfunction "AGND_99") (pintype "power_in"))
      (node (ref "U3") (pin "6") (pinfunction "GND_6") (pintype "bidirectional"))
      (node (ref "U3") (pin "9") (pinfunction "PAD_9") (pintype "bidirectional"))
      (node (ref "U4") (pin "P03") (pinfunction "B6_P03") (pintype "bidirectional"))
      (node (ref "U4") (pin "P04") (pinfunction "GND_P04") (pintype "bidirectional"))
      (node (ref "U4") (pin "P09") (pinfunction "VSS_P09") (pintype "bidirectional"))
      (node (ref "U4") (pin "P10") (pinfunction "B5_P10") (pintype "bidirectional"))
      (node (ref "U4") (pin "P13") (pinfunction "B3_P13") (pintype "bidirectional"))
      (node (ref "U4") (pin "P16") (pinfunction "B1_P16") (pintype "bidirectional"))
      (node (ref "U4") (pin "P21") (pinfunction "B2_P21") (pintype "bidirectional"))
      (node (ref "U4") (pin "P24") (pinfunction "B4_P24") (pintype "bidirectional"))
      (node (ref "U5") (pin "19") (pinfunction "GND2_19") (pintype "power_in"))
      (node (ref "U5") (pin "33") (pinfunction "TH-PAD_33") (pintype "power_in"))
      (node (ref "U5") (pin "6") (pinfunction "GND1_6") (pintype "power_in"))
      (node (ref "U6") (pin "19") (pinfunction "GND2_19") (pintype "power_in"))
      (node (ref "U6") (pin "33") (pinfunction "TH-PAD_33") (pintype "power_in"))
      (node (ref "U6") (pin "6") (pinfunction "GND1_6") (pintype "power_in"))
      (node (ref "U7") (pin "19") (pinfunction "GND2_19") (pintype "power_in"))
      (node (ref "U7") (pin "33") (pinfunction "TH-PAD_33") (pintype "power_in"))
      (node (ref "U7") (pin "6") (pinfunction "GND1_6") (pintype "power_in"))
      (node (ref "U8") (pin "19") (pinfunction "GND2_19") (pintype "power_in"))
      (node (ref "U8") (pin "33") (pinfunction "TH-PAD_33") (pintype "power_in"))
      (node (ref "U8") (pin "6") (pinfunction "GND1_6") (pintype "power_in"))
      (node (ref "U9") (pin "19") (pinfunction "GND2_19") (pintype "power_in"))
      (node (ref "U9") (pin "33") (pinfunction "TH-PAD_33") (pintype "power_in"))
      (node (ref "U9") (pin "6") (pinfunction "GND1_6") (pintype "power_in"))
      (node (ref "X1") (pin "1") (pinfunction "S_1") (pintype "passive"))
      (node (ref "X10") (pin "2") (pinfunction "S_2") (pintype "passive"))
      (node (ref "X12") (pin "7") (pinfunction "7_7") (pintype "passive"))
      (node (ref "X13") (pin "3") (pinfunction "3_3") (pintype "passive"))
      (node (ref "X13") (pin "4") (pinfunction "4_4") (pintype "passive"))
      (node (ref "X18") (pin "6") (pinfunction "6_6") (pintype "passive"))
      (node (ref "X20") (pin "2") (pinfunction "2_2") (pintype "passive"))
      (node (ref "X21") (pin "2") (pinfunction "S_2") (pintype "passive"))
      (node (ref "X22") (pin "2") (pinfunction "S_2") (pintype "passive"))
      (node (ref "X23") (pin "2") (pinfunction "S_2") (pintype "passive"))
      (node (ref "X24") (pin "2") (pinfunction "S_2") (pintype "passive"))
      (node (ref "X25") (pin "2") (pinfunction "S_2") (pintype "passive"))
      (node (ref "X26") (pin "2") (pinfunction "S_2") (pintype "passive"))
      (node (ref "X27") (pin "1") (pinfunction "S_1") (pintype "passive"))
      (node (ref "X28") (pin "1") (pinfunction "S_1") (pintype "passive"))
      (node (ref "X29") (pin "1") (pinfunction "S_1") (pintype "passive"))
      (node (ref "X3") (pin "1") (pinfunction "S_1") (pintype "passive"))
      (node (ref "X30") (pin "1") (pinfunction "S_1") (pintype "passive"))
      (node (ref "X31") (pin "2") (pinfunction "2_2") (pintype "passive"))
      (node (ref "X32") (pin "2") (pinfunction "2_2") (pintype "passive"))
      (node (ref "X33") (pin "2") (pinfunction "1_2") (pintype "passive"))
      (node (ref "X33") (pin "4") (pinfunction "1_4") (pintype "passive"))
      (node (ref "X33") (pin "6") (pinfunction "1_6") (pintype "passive"))
      (node (ref "X34") (pin "2") (pinfunction "2_2") (pintype "passive"))
      (node (ref "X39") (pin "2") (pinfunction "2_2") (pintype "passive"))
      (node (ref "X40") (pin "2") (pinfunction "2_2") (pintype "passive"))
      (node (ref "Y1") (pin "2") (pinfunction "GND_2") (pintype "passive"))
      (node (ref "Y1") (pin "4") (pinfunction "GND_4") (pintype "passive"))
    )
    (net (code "131") (name "GND1") (class "Default")
      (node (ref "C11") (pin "2") (pinfunction "2_2") (pintype "passive"))
      (node (ref "C12") (pin "2") (pinfunction "2_2") (pintype "passive"))
      (node (ref "C13") (pin "2") (pinfunction "2_2") (pintype "passive"))
      (node (ref "C14") (pin "2") (pinfunction "2_2") (pintype "passive"))
      (node (ref "C15") (pin "2") (pinfunction "2_2") (pintype "passive"))
      (node (ref "C16") (pin "2") (pinfunction "2_2") (pintype "passive"))
      (node (ref "C19") (pin "2") (pinfunction "2_2") (pintype "passive"))
      (node (ref "C2") (pin "1") (pinfunction "1_1") (pintype "passive"))
      (node (ref "C5") (pin "2") (pinfunction "2_2") (pintype "passive"))
      (node (ref "C63") (pin "2") (pinfunction "2_2") (pintype "passive"))
      (node (ref "D40") (pin "A") (pinfunction "1_A") (pintype "passive"))
      (node (ref "R72") (pin "1") (pinfunction "1_1") (pintype "passive"))
      (node (ref "RN5") (pin "8") (pinfunction "2_8") (pintype "passive"))
      (node (ref "U1") (pin "28") (pinfunction "UGND_28") (pintype "power_in"))
      (node (ref "U1") (pin "3") (pinfunction "GND_3") (pintype "power_in"))
      (node (ref "U1") (pin "33") (pinfunction "PAD_33") (pintype "power_in"))
      (node (ref "U10") (pin "2") (pinfunction "GND1A_2") (pintype "bidirectional"))
      (node (ref "U10") (pin "4") (pinfunction "VIB_4") (pintype "bidirectional"))
      (node (ref "U10") (pin "8") (pinfunction "GND1B_8") (pintype "bidirectional"))
      (node (ref "X16") (pin "3") (pinfunction "3_3") (pintype "passive"))
      (node (ref "X16") (pin "4") (pinfunction "4_4") (pintype "passive"))
      (node (ref "X17") (pin "6") (pinfunction "6_6") (pintype "passive"))
      (node (ref "X2") (pin "4") (pinfunction "4_4") (pintype "bidirectional"))
      (node (ref "Y2") (pin "2") (pinfunction "GND_2") (pintype "passive"))
      (node (ref "Y2") (pin "4") (pinfunction "GND_4") (pintype "passive"))
    )
    (net (code "132") (name "Net-(CF1-Pad3)") (class "Default")
      (node (ref "CF1") (pin "3") (pinfunction "3_3") (pintype "passive"))
      (node (ref "X8") (pin "1") (pinfunction "1_1") (pintype "passive"))
    )
    (net (code "133") (name "Net-(CF5-Pad3)") (class "Default")
      (node (ref "CF5") (pin "3") (pinfunction "3_3") (pintype "passive"))
      (node (ref "X4") (pin "1") (pinfunction "1_1") (pintype "passive"))
    )
    (net (code "134") (name "Net-(CF9-Pad3)") (class "Default")
      (node (ref "CF9") (pin "3") (pinfunction "3_3") (pintype "passive"))
      (node (ref "X14") (pin "1") (pinfunction "1_1") (pintype "passive"))
      (node (ref "X15") (pin "1") (pinfunction "1_1") (pintype "passive"))
    )
    (net (code "135") (name "Net-(CF13-Pad3)") (class "Default")
      (node (ref "CF13") (pin "3") (pinfunction "3_3") (pintype "passive"))
      (node (ref "X6") (pin "1") (pinfunction "1_1") (pintype "passive"))
    )
    (net (code "136") (name "Net-(CF17-Pad3)") (class "Default")
      (node (ref "CF17") (pin "3") (pinfunction "3_3") (pintype "passive"))
      (node (ref "X7") (pin "1") (pinfunction "1_1") (pintype "passive"))
    )
    (net (code "137") (name "Net-(F4-1)") (class "Default")
      (node (ref "F4") (pin "P$1") (pinfunction "1_P$1") (pintype "passive"))
      (node (ref "X33") (pin "5") (pinfunction "1_5") (pintype "passive"))
    )
    (net (code "138") (name "Net-(L1-1)") (class "Default")
      (node (ref "L1") (pin "P$1") (pinfunction "1_P$1") (pintype "passive"))
      (node (ref "X33") (pin "1") (pinfunction "1_1") (pintype "passive"))
    )
    (net (code "139") (name "Net-(L1-2)") (class "Default")
      (node (ref "F2") (pin "P$1") (pinfunction "P$1_P$1") (pintype "bidirectional"))
      (node (ref "L1") (pin "P$2") (pinfunction "2_P$2") (pintype "passive"))
    )
    (net (code "140") (name "Net-(L3-1)") (class "Default")
      (node (ref "C35") (pin "2") (pinfunction "2_2") (pintype "passive"))
      (node (ref "D20") (pin "C") (pinfunction "C_C") (pintype "passive"))
      (node (ref "L3") (pin "P$1") (pinfunction "1_P$1") (pintype "passive"))
      (node (ref "U3") (pin "8") (pinfunction "SWITCH_8") (pintype "bidirectional"))
    )
    (net (code "141") (name "Net-(L4-1)") (class "Default")
      (node (ref "L4") (pin "P$1") (pinfunction "1_P$1") (pintype "passive"))
      (node (ref "X33") (pin "3") (pinfunction "1_3") (pintype "passive"))
    )
    (net (code "142") (name "Net-(L4-2)") (class "Default")
      (node (ref "F3") (pin "P$1") (pinfunction "P$1_P$1") (pintype "bidirectional"))
      (node (ref "L4") (pin "P$2") (pinfunction "2_P$2") (pintype "passive"))
    )
    (net (code "143") (name "Net-(LED1-PadA)") (class "Default")
      (node (ref "LED1") (pin "A") (pinfunction "A_A") (pintype "passive"))
      (node (ref "R33") (pin "2") (pinfunction "2_2") (pintype "passive"))
    )
    (net (code "144") (name "Net-(LED2-PadA)") (class "Default")
      (node (ref "LED2") (pin "A") (pinfunction "A_A") (pintype "passive"))
      (node (ref "R40") (pin "1") (pinfunction "1_1") (pintype "passive"))
    )
    (net (code "145") (name "Net-(LED3-PadA)") (class "Default")
      (node (ref "LED3") (pin "A") (pinfunction "A_A") (pintype "passive"))
      (node (ref "R50") (pin "1") (pinfunction "1_1") (pintype "passive"))
    )
    (net (code "146") (name "Net-(LED4-PadA)") (class "Default")
      (node (ref "LED4") (pin "A") (pinfunction "A_A") (pintype "passive"))
      (node (ref "R41") (pin "1") (pinfunction "1_1") (pintype "passive"))
    )
    (net (code "147") (name "Net-(LED5-PadA)") (class "Default")
      (node (ref "LED5") (pin "A") (pinfunction "A_A") (pintype "passive"))
      (node (ref "R55") (pin "1") (pinfunction "1_1") (pintype "passive"))
    )
    (net (code "148") (name "Net-(LED6-PadA)") (class "Default")
      (node (ref "LED6") (pin "A") (pinfunction "A_A") (pintype "passive"))
      (node (ref "R58") (pin "1") (pinfunction "1_1") (pintype "passive"))
    )
    (net (code "149") (name "Net-(LED7-PadA)") (class "Default")
      (node (ref "LED7") (pin "A") (pinfunction "A_A") (pintype "passive"))
      (node (ref "R35") (pin "2") (pinfunction "2_2") (pintype "passive"))
    )
    (net (code "150") (name "Net-(LED8-PadA)") (class "Default")
      (node (ref "LED8") (pin "A") (pinfunction "A_A") (pintype "passive"))
      (node (ref "R69") (pin "1") (pinfunction "1_1") (pintype "passive"))
    )
    (net (code "151") (name "Net-(Q1-D)") (class "Default")
      (node (ref "D6") (pin "A") (pinfunction "A_A") (pintype "passive"))
      (node (ref "LED2") (pin "C") (pinfunction "C_C") (pintype "passive"))
      (node (ref "Q1") (pin "MB") (pinfunction "D_MB") (pintype "passive"))
      (node (ref "X11") (pin "1") (pinfunction "1_1") (pintype "passive"))
      (node (ref "X35") (pin "1") (pinfunction "1_1") (pintype "passive"))
    )
    (net (code "152") (name "Net-(Q1-G)") (class "Default")
      (node (ref "Q1") (pin "4") (pinfunction "G_4") (pintype "passive"))
      (node (ref "R42") (pin "2") (pinfunction "2_2") (pintype "passive"))
    )
    (net (code "153") (name "Net-(Q2-D)") (class "Default")
      (node (ref "D3") (pin "A") (pinfunction "A_A") (pintype "passive"))
      (node (ref "LED3") (pin "C") (pinfunction "C_C") (pintype "passive"))
      (node (ref "Q2") (pin "MB") (pinfunction "D_MB") (pintype "passive"))
      (node (ref "X11") (pin "3") (pinfunction "1_3") (pintype "passive"))
      (node (ref "X36") (pin "1") (pinfunction "1_1") (pintype "passive"))
    )
    (net (code "154") (name "Net-(Q2-G)") (class "Default")
      (node (ref "Q2") (pin "4") (pinfunction "G_4") (pintype "passive"))
      (node (ref "R48") (pin "2") (pinfunction "2_2") (pintype "passive"))
    )
    (net (code "155") (name "Net-(Q3-D)") (class "Default")
      (node (ref "D1") (pin "A") (pinfunction "A_A") (pintype "passive"))
      (node (ref "LED4") (pin "C") (pinfunction "C_C") (pintype "passive"))
      (node (ref "Q3") (pin "MB") (pinfunction "D_MB") (pintype "passive"))
      (node (ref "X11") (pin "5") (pinfunction "1_5") (pintype "passive"))
      (node (ref "X37") (pin "1") (pinfunction "1_1") (pintype "passive"))
    )
    (net (code "156") (name "Net-(Q3-G)") (class "Default")
      (node (ref "Q3") (pin "4") (pinfunction "G_4") (pintype "passive"))
      (node (ref "R51") (pin "2") (pinfunction "2_2") (pintype "passive"))
    )
    (net (code "157") (name "Net-(Q4-D)") (class "Default")
      (node (ref "LED5") (pin "C") (pinfunction "C_C") (pintype "passive"))
      (node (ref "Q4") (pin "3") (pinfunction "D_3") (pintype "passive"))
      (node (ref "X11") (pin "7") (pinfunction "1_7") (pintype "passive"))
    )
    (net (code "158") (name "Net-(Q4-G)") (class "Default")
      (node (ref "Q4") (pin "1") (pinfunction "G_1") (pintype "passive"))
      (node (ref "R53") (pin "2") (pinfunction "2_2") (pintype "passive"))
    )
    (net (code "159") (name "Net-(Q5-D)") (class "Default")
      (node (ref "D10") (pin "A") (pinfunction "A_A") (pintype "passive"))
      (node (ref "LED6") (pin "C") (pinfunction "C_C") (pintype "passive"))
      (node (ref "Q5") (pin "MB") (pinfunction "D_MB") (pintype "passive"))
      (node (ref "X11") (pin "9") (pinfunction "1_9") (pintype "passive"))
      (node (ref "X38") (pin "1") (pinfunction "1_1") (pintype "passive"))
    )
    (net (code "160") (name "Net-(Q5-G)") (class "Default")
      (node (ref "Q5") (pin "4") (pinfunction "G_4") (pintype "passive"))
      (node (ref "R56") (pin "2") (pinfunction "2_2") (pintype "passive"))
    )
    (net (code "161") (name "Net-(Q8-D)") (class "Default")
      (node (ref "LED8") (pin "C") (pinfunction "C_C") (pintype "passive"))
      (node (ref "Q8") (pin "3") (pinfunction "D_3") (pintype "passive"))
      (node (ref "X9") (pin "1") (pinfunction "S_1") (pintype "passive"))
    )
    (net (code "162") (name "Net-(Q8-G)") (class "Default")
      (node (ref "Q8") (pin "1") (pinfunction "G_1") (pintype "passive"))
      (node (ref "R70") (pin "2") (pinfunction "2_2") (pintype "passive"))
    )
    (net (code "163") (name "Net-(RN5B-2)") (class "Default")
      (node (ref "LED10") (pin "A") (pinfunction "A_A") (pintype "passive"))
      (node (ref "RN5") (pin "7") (pinfunction "2_7") (pintype "passive"))
    )
    (net (code "164") (name "Net-(RN5C-2)") (class "Default")
      (node (ref "LED9") (pin "A") (pinfunction "A_A") (pintype "passive"))
      (node (ref "RN5") (pin "6") (pinfunction "2_6") (pintype "passive"))
    )
    (net (code "165") (name "Net-(U1-XTAL1)") (class "Default")
      (node (ref "C13") (pin "1") (pinfunction "1_1") (pintype "passive"))
      (node (ref "U1") (pin "1") (pinfunction "XTAL1_1") (pintype "bidirectional"))
      (node (ref "Y2") (pin "1") (pinfunction "C1_1") (pintype "passive"))
    )
    (net (code "166") (name "Net-(U1-XTAL2(PC0))") (class "Default")
      (node (ref "C12") (pin "1") (pinfunction "1_1") (pintype "passive"))
      (node (ref "U1") (pin "2") (pinfunction "XTAL2(PC0)_2") (pintype "bidirectional"))
      (node (ref "Y2") (pin "3") (pinfunction "C2_3") (pintype "passive"))
    )
    (net (code "167") (name "Net-(U2-AVCC)") (class "Default")
      (node (ref "C26") (pin "1") (pinfunction "1_1") (pintype "passive"))
      (node (ref "L2") (pin "2") (pinfunction "2_2") (pintype "passive"))
      (node (ref "U2") (pin "100") (pinfunction "AVCC_100") (pintype "power_in"))
    )
    (net (code "168") (name "Net-(U2-XTAL1)") (class "Default")
      (node (ref "C57") (pin "1") (pinfunction "1_1") (pintype "passive"))
      (node (ref "U2") (pin "34") (pinfunction "XTAL1_34") (pintype "input"))
      (node (ref "Y1") (pin "1") (pinfunction "C1_1") (pintype "passive"))
    )
    (net (code "169") (name "Net-(U2-XTAL2)") (class "Default")
      (node (ref "C58") (pin "1") (pinfunction "1_1") (pintype "passive"))
      (node (ref "U2") (pin "33") (pinfunction "XTAL2_33") (pintype "output"))
      (node (ref "Y1") (pin "3") (pinfunction "C2_3") (pintype "passive"))
    )
    (net (code "170") (name "Net-(U3-BOOT)") (class "Default")
      (node (ref "C35") (pin "1") (pinfunction "1_1") (pintype "passive"))
      (node (ref "U3") (pin "1") (pinfunction "BOOT_1") (pintype "bidirectional"))
    )
    (net (code "171") (name "Net-(U3-ENABLE)") (class "Default")
      (node (ref "JP3") (pin "2") (pinfunction "2_2") (pintype "passive"))
      (node (ref "R3") (pin "1") (pinfunction "1_1") (pintype "passive"))
      (node (ref "U3") (pin "5") (pinfunction "ENABLE_5") (pintype "bidirectional"))
    )
    (net (code "172") (name "Net-(U3-FEEDBACK)") (class "Default")
      (node (ref "R11") (pin "1") (pinfunction "1_1") (pintype "passive"))
      (node (ref "R13") (pin "1") (pinfunction "1_1") (pintype "passive"))
      (node (ref "U3") (pin "4") (pinfunction "FEEDBACK_4") (pintype "bidirectional"))
    )
    (net (code "173") (name "Net-(U4-A1)") (class "Default")
      (node (ref "R30") (pin "2") (pinfunction "2_2") (pintype "passive"))
      (node (ref "U4") (pin "P01") (pinfunction "A6_P01") (pintype "bidirectional"))
      (node (ref "U4") (pin "P12") (pinfunction "A5_P12") (pintype "bidirectional"))
      (node (ref "U4") (pin "P15") (pinfunction "A3_P15") (pintype "bidirectional"))
      (node (ref "U4") (pin "P18") (pinfunction "A1_P18") (pintype "bidirectional"))
      (node (ref "U4") (pin "P19") (pinfunction "A2_P19") (pintype "bidirectional"))
      (node (ref "U4") (pin "P22") (pinfunction "A4_P22") (pintype "bidirectional"))
    )
    (net (code "174") (name "Net-(U5-CP1)") (class "Default")
      (node (ref "C28") (pin "1") (pinfunction "1_1") (pintype "passive"))
      (node (ref "U5") (pin "7") (pinfunction "CP1_7") (pintype "bidirectional"))
    )
    (net (code "175") (name "Net-(U5-CP2)") (class "Default")
      (node (ref "C28") (pin "2") (pinfunction "2_2") (pintype "passive"))
      (node (ref "U5") (pin "8") (pinfunction "CP2_8") (pintype "bidirectional"))
    )
    (net (code "176") (name "Net-(U5-OUT1A)") (class "Default")
      (node (ref "CF3") (pin "1") (pinfunction "1_1") (pintype "passive"))
      (node (ref "D9") (pin "C") (pinfunction "C_C") (pintype "passive"))
      (node (ref "U5") (pin "27") (pinfunction "OUT1A_27") (pintype "output"))
    )
    (net (code "177") (name "Net-(U5-OUT1B)") (class "Default")
      (node (ref "CF4") (pin "1") (pinfunction "1_1") (pintype "passive"))
      (node (ref "D21") (pin "C") (pinfunction "C_C") (pintype "passive"))
      (node (ref "U5") (pin "24") (pinfunction "OUT1B_24") (pintype "output"))
    )
    (net (code "178") (name "Net-(U5-OUT2A)") (class "Default")
      (node (ref "CF2") (pin "1") (pinfunction "1_1") (pintype "passive"))
      (node (ref "D23") (pin "C") (pinfunction "C_C") (pintype "passive"))
      (node (ref "U5") (pin "30") (pinfunction "OUT2A_30") (pintype "output"))
    )
    (net (code "179") (name "Net-(U5-OUT2B)") (class "Default")
      (node (ref "CF1") (pin "1") (pinfunction "1_1") (pintype "passive"))
      (node (ref "D22") (pin "C") (pinfunction "C_C") (pintype "passive"))
      (node (ref "U5") (pin "1") (pinfunction "OUT2B_1") (pintype "output"))
    )
    (net (code "180") (name "Net-(U5-RESET)") (class "Default")
      (node (ref "C24") (pin "1") (pinfunction "1_1") (pintype "passive"))
      (node (ref "R29") (pin "1") (pinfunction "1_1") (pintype "passive"))
      (node (ref "U5") (pin "13") (pinfunction "RESET_13") (pintype "input"))
      (node (ref "U5") (pin "15") (pinfunction "SLEEP_15") (pintype "input"))
      (node (ref "U5") (pin "16") (pinfunction "VDD_16") (pintype "power_in"))
    )
    (net (code "181") (name "Net-(U5-ROSC)") (class "Default")
      (node (ref "R18") (pin "2") (pinfunction "2_2") (pintype "passive"))
      (node (ref "U5") (pin "14") (pinfunction "ROSC_14") (pintype "input"))
    )
    (net (code "182") (name "Net-(U5-SENSE1)") (class "Default")
      (node (ref "R7") (pin "1") (pinfunction "1_1") (pintype "passive"))
      (node (ref "U5") (pin "25") (pinfunction "SENSE1_25") (pintype "input"))
    )
    (net (code "183") (name "Net-(U5-SENSE2)") (class "Default")
      (node (ref "R4") (pin "1") (pinfunction "1_1") (pintype "passive"))
      (node (ref "U5") (pin "32") (pinfunction "SENSE2_32") (pintype "input"))
    )
    (net (code "184") (name "Net-(U5-VCP)") (class "Default")
      (node (ref "C27") (pin "2") (pinfunction "2_2") (pintype "passive"))
      (node (ref "U5") (pin "9") (pinfunction "VCP_9") (pintype "bidirectional"))
    )
    (net (code "185") (name "Net-(U5-VREG)") (class "Default")
      (node (ref "C31") (pin "2") (pinfunction "2_2") (pintype "passive"))
      (node (ref "U5") (pin "10") (pinfunction "VREG_10") (pintype "input"))
    )
    (net (code "186") (name "Net-(U6-CP1)") (class "Default")
      (node (ref "C33") (pin "1") (pinfunction "1_1") (pintype "passive"))
      (node (ref "U6") (pin "7") (pinfunction "CP1_7") (pintype "bidirectional"))
    )
    (net (code "187") (name "Net-(U6-CP2)") (class "Default")
      (node (ref "C33") (pin "2") (pinfunction "2_2") (pintype "passive"))
      (node (ref "U6") (pin "8") (pinfunction "CP2_8") (pintype "bidirectional"))
    )
    (net (code "188") (name "Net-(U6-OUT1A)") (class "Default")
      (node (ref "CF7") (pin "1") (pinfunction "1_1") (pintype "passive"))
      (node (ref "D25") (pin "C") (pinfunction "C_C") (pintype "passive"))
      (node (ref "U6") (pin "27") (pinfunction "OUT1A_27") (pintype "output"))
    )
    (net (code "189") (name "Net-(U6-OUT1B)") (class "Default")
      (node (ref "CF8") (pin "1") (pinfunction "1_1") (pintype "passive"))
      (node (ref "D24") (pin "C") (pinfunction "C_C") (pintype "passive"))
      (node (ref "U6") (pin "24") (pinfunction "OUT1B_24") (pintype "output"))
    )
    (net (code "190") (name "Net-(U6-OUT2A)") (class "Default")
      (node (ref "CF6") (pin "1") (pinfunction "1_1") (pintype "passive"))
      (node (ref "D27") (pin "C") (pinfunction "C_C") (pintype "passive"))
      (node (ref "U6") (pin "30") (pinfunction "OUT2A_30") (pintype "output"))
    )
    (net (code "191") (name "Net-(U6-OUT2B)") (class "Default")
      (node (ref "CF5") (pin "1") (pinfunction "1_1") (pintype "passive"))
      (node (ref "D26") (pin "C") (pinfunction "C_C") (pintype "passive"))
      (node (ref "U6") (pin "1") (pinfunction "OUT2B_1") (pintype "output"))
    )
    (net (code "192") (name "Net-(U6-RESET)") (class "Default")
      (node (ref "C23") (pin "1") (pinfunction "1_1") (pintype "passive"))
      (node (ref "R65") (pin "1") (pinfunction "1_1") (pintype "passive"))
      (node (ref "U6") (pin "13") (pinfunction "RESET_13") (pintype "input"))
      (node (ref "U6") (pin "15") (pinfunction "SLEEP_15") (pintype "input"))
      (node (ref "U6") (pin "16") (pinfunction "VDD_16") (pintype "power_in"))
    )
    (net (code "193") (name "Net-(U6-ROSC)") (class "Default")
      (node (ref "R12") (pin "2") (pinfunction "2_2") (pintype "passive"))
      (node (ref "U6") (pin "14") (pinfunction "ROSC_14") (pintype "input"))
    )
    (net (code "194") (name "Net-(U6-SENSE1)") (class "Default")
      (node (ref "R10") (pin "1") (pinfunction "1_1") (pintype "passive"))
      (node (ref "U6") (pin "25") (pinfunction "SENSE1_25") (pintype "input"))
    )
    (net (code "195") (name "Net-(U6-SENSE2)") (class "Default")
      (node (ref "R8") (pin "1") (pinfunction "1_1") (pintype "passive"))
      (node (ref "U6") (pin "32") (pinfunction "SENSE2_32") (pintype "input"))
    )
    (net (code "196") (name "Net-(U6-VCP)") (class "Default")
      (node (ref "C32") (pin "2") (pinfunction "2_2") (pintype "passive"))
      (node (ref "U6") (pin "9") (pinfunction "VCP_9") (pintype "bidirectional"))
    )
    (net (code "197") (name "Net-(U6-VREG)") (class "Default")
      (node (ref "C36") (pin "2") (pinfunction "2_2") (pintype "passive"))
      (node (ref "U6") (pin "10") (pinfunction "VREG_10") (pintype "input"))
    )
    (net (code "198") (name "Net-(U7-CP1)") (class "Default")
      (node (ref "C38") (pin "1") (pinfunction "1_1") (pintype "passive"))
      (node (ref "U7") (pin "7") (pinfunction "CP1_7") (pintype "bidirectional"))
    )
    (net (code "199") (name "Net-(U7-CP2)") (class "Default")
      (node (ref "C38") (pin "2") (pinfunction "2_2") (pintype "passive"))
      (node (ref "U7") (pin "8") (pinfunction "CP2_8") (pintype "bidirectional"))
    )
    (net (code "200") (name "Net-(U7-OUT1A)") (class "Default")
      (node (ref "CF11") (pin "1") (pinfunction "1_1") (pintype "passive"))
      (node (ref "D28") (pin "C") (pinfunction "C_C") (pintype "passive"))
      (node (ref "U7") (pin "27") (pinfunction "OUT1A_27") (pintype "output"))
    )
    (net (code "201") (name "Net-(U7-OUT1B)") (class "Default")
      (node (ref "CF12") (pin "1") (pinfunction "1_1") (pintype "passive"))
      (node (ref "D29") (pin "C") (pinfunction "C_C") (pintype "passive"))
      (node (ref "U7") (pin "24") (pinfunction "OUT1B_24") (pintype "output"))
    )
    (net (code "202") (name "Net-(U7-OUT2A)") (class "Default")
      (node (ref "CF10") (pin "1") (pinfunction "1_1") (pintype "passive"))
      (node (ref "D30") (pin "C") (pinfunction "C_C") (pintype "passive"))
      (node (ref "U7") (pin "30") (pinfunction "OUT2A_30") (pintype "output"))
    )
    (net (code "203") (name "Net-(U7-OUT2B)") (class "Default")
      (node (ref "CF9") (pin "1") (pinfunction "1_1") (pintype "passive"))
      (node (ref "D31") (pin "C") (pinfunction "C_C") (pintype "passive"))
      (node (ref "U7") (pin "1") (pinfunction "OUT2B_1") (pintype "output"))
    )
    (net (code "204") (name "Net-(U7-RESET)") (class "Default")
      (node (ref "C18") (pin "1") (pinfunction "1_1") (pintype "passive"))
      (node (ref "R66") (pin "1") (pinfunction "1_1") (pintype "passive"))
      (node (ref "U7") (pin "13") (pinfunction "RESET_13") (pintype "input"))
      (node (ref "U7") (pin "15") (pinfunction "SLEEP_15") (pintype "input"))
      (node (ref "U7") (pin "16") (pinfunction "VDD_16") (pintype "power_in"))
    )
    (net (code "205") (name "Net-(U7-ROSC)") (class "Default")
      (node (ref "R17") (pin "2") (pinfunction "2_2") (pintype "passive"))
      (node (ref "U7") (pin "14") (pinfunction "ROSC_14") (pintype "input"))
    )
    (net (code "206") (name "Net-(U7-SENSE1)") (class "Default")
      (node (ref "R15") (pin "1") (pinfunction "1_1") (pintype "passive"))
      (node (ref "U7") (pin "25") (pinfunction "SENSE1_25") (pintype "input"))
    )
    (net (code "207") (name "Net-(U7-SENSE2)") (class "Default")
      (node (ref "R14") (pin "1") (pinfunction "1_1") (pintype "passive"))
      (node (ref "U7") (pin "32") (pinfunction "SENSE2_32") (pintype "input"))
    )
    (net (code "208") (name "Net-(U7-VCP)") (class "Default")
      (node (ref "C37") (pin "2") (pinfunction "2_2") (pintype "passive"))
      (node (ref "U7") (pin "9") (pinfunction "VCP_9") (pintype "bidirectional"))
    )
    (net (code "209") (name "Net-(U7-VREG)") (class "Default")
      (node (ref "C41") (pin "2") (pinfunction "2_2") (pintype "passive"))
      (node (ref "U7") (pin "10") (pinfunction "VREG_10") (pintype "input"))
    )
    (net (code "210") (name "Net-(U8-CP1)") (class "Default")
      (node (ref "C43") (pin "1") (pinfunction "1_1") (pintype "passive"))
      (node (ref "U8") (pin "7") (pinfunction "CP1_7") (pintype "bidirectional"))
    )
    (net (code "211") (name "Net-(U8-CP2)") (class "Default")
      (node (ref "C43") (pin "2") (pinfunction "2_2") (pintype "passive"))
      (node (ref "U8") (pin "8") (pinfunction "CP2_8") (pintype "bidirectional"))
    )
    (net (code "212") (name "Net-(U8-OUT1A)") (class "Default")
      (node (ref "CF15") (pin "1") (pinfunction "1_1") (pintype "passive"))
      (node (ref "D32") (pin "C") (pinfunction "C_C") (pintype "passive"))
      (node (ref "U8") (pin "27") (pinfunction "OUT1A_27") (pintype "output"))
    )
    (net (code "213") (name "Net-(U8-OUT1B)") (class "Default")
      (node (ref "CF16") (pin "1") (pinfunction "1_1") (pintype "passive"))
      (node (ref "D33") (pin "C") (pinfunction "C_C") (pintype "passive"))
      (node (ref "U8") (pin "24") (pinfunction "OUT1B_24") (pintype "output"))
    )
    (net (code "214") (name "Net-(U8-OUT2A)") (class "Default")
      (node (ref "CF14") (pin "1") (pinfunction "1_1") (pintype "passive"))
      (node (ref "D35") (pin "C") (pinfunction "C_C") (pintype "passive"))
      (node (ref "U8") (pin "30") (pinfunction "OUT2A_30") (pintype "output"))
    )
    (net (code "215") (name "Net-(U8-OUT2B)") (class "Default")
      (node (ref "CF13") (pin "1") (pinfunction "1_1") (pintype "passive"))
      (node (ref "D34") (pin "C") (pinfunction "C_C") (pintype "passive"))
      (node (ref "U8") (pin "1") (pinfunction "OUT2B_1") (pintype "output"))
    )
    (net (code "216") (name "Net-(U8-RESET)") (class "Default")
      (node (ref "C17") (pin "1") (pinfunction "1_1") (pintype "passive"))
      (node (ref "R67") (pin "1") (pinfunction "1_1") (pintype "passive"))
      (node (ref "U8") (pin "13") (pinfunction "RESET_13") (pintype "input"))
      (node (ref "U8") (pin "15") (pinfunction "SLEEP_15") (pintype "input"))
      (node (ref "U8") (pin "16") (pinfunction "VDD_16") (pintype "power_in"))
    )
    (net (code "217") (name "Net-(U8-ROSC)") (class "Default")
      (node (ref "R22") (pin "2") (pinfunction "2_2") (pintype "passive"))
      (node (ref "U8") (pin "14") (pinfunction "ROSC_14") (pintype "input"))
    )
    (net (code "218") (name "Net-(U8-SENSE1)") (class "Default")
      (node (ref "R20") (pin "1") (pinfunction "1_1") (pintype "passive"))
      (node (ref "U8") (pin "25") (pinfunction "SENSE1_25") (pintype "input"))
    )
    (net (code "219") (name "Net-(U8-SENSE2)") (class "Default")
      (node (ref "R19") (pin "1") (pinfunction "1_1") (pintype "passive"))
      (node (ref "U8") (pin "32") (pinfunction "SENSE2_32") (pintype "input"))
    )
    (net (code "220") (name "Net-(U8-VCP)") (class "Default")
      (node (ref "C42") (pin "2") (pinfunction "2_2") (pintype "passive"))
      (node (ref "U8") (pin "9") (pinfunction "VCP_9") (pintype "bidirectional"))
    )
    (net (code "221") (name "Net-(U8-VREG)") (class "Default")
      (node (ref "C46") (pin "2") (pinfunction "2_2") (pintype "passive"))
      (node (ref "U8") (pin "10") (pinfunction "VREG_10") (pintype "input"))
    )
    (net (code "222") (name "Net-(U9-CP1)") (class "Default")
      (node (ref "C48") (pin "1") (pinfunction "1_1") (pintype "passive"))
      (node (ref "U9") (pin "7") (pinfunction "CP1_7") (pintype "bidirectional"))
    )
    (net (code "223") (name "Net-(U9-CP2)") (class "Default")
      (node (ref "C48") (pin "2") (pinfunction "2_2") (pintype "passive"))
      (node (ref "U9") (pin "8") (pinfunction "CP2_8") (pintype "bidirectional"))
    )
    (net (code "224") (name "Net-(U9-OUT1A)") (class "Default")
      (node (ref "CF19") (pin "1") (pinfunction "1_1") (pintype "passive"))
      (node (ref "D38") (pin "C") (pinfunction "C_C") (pintype "passive"))
      (node (ref "U9") (pin "27") (pinfunction "OUT1A_27") (pintype "output"))
    )
    (net (code "225") (name "Net-(U9-OUT1B)") (class "Default")
      (node (ref "CF20") (pin "1") (pinfunction "1_1") (pintype "passive"))
      (node (ref "D39") (pin "C") (pinfunction "C_C") (pintype "passive"))
      (node (ref "U9") (pin "24") (pinfunction "OUT1B_24") (pintype "output"))
    )
    (net (code "226") (name "Net-(U9-OUT2A)") (class "Default")
      (node (ref "CF18") (pin "1") (pinfunction "1_1") (pintype "passive"))
      (node (ref "D37") (pin "C") (pinfunction "C_C") (pintype "passive"))
      (node (ref "U9") (pin "30") (pinfunction "OUT2A_30") (pintype "output"))
    )
    (net (code "227") (name "Net-(U9-OUT2B)") (class "Default")
      (node (ref "CF17") (pin "1") (pinfunction "1_1") (pintype "passive"))
      (node (ref "D36") (pin "C") (pinfunction "C_C") (pintype "passive"))
      (node (ref "U9") (pin "1") (pinfunction "OUT2B_1") (pintype "output"))
    )
    (net (code "228") (name "Net-(U9-RESET)") (class "Default")
      (node (ref "C4") (pin "1") (pinfunction "1_1") (pintype "passive"))
      (node (ref "R68") (pin "1") (pinfunction "1_1") (pintype "passive"))
      (node (ref "U9") (pin "13") (pinfunction "RESET_13") (pintype "input"))
      (node (ref "U9") (pin "15") (pinfunction "SLEEP_15") (pintype "input"))
      (node (ref "U9") (pin "16") (pinfunction "VDD_16") (pintype "power_in"))
    )
    (net (code "229") (name "Net-(U9-ROSC)") (class "Default")
      (node (ref "R26") (pin "2") (pinfunction "2_2") (pintype "passive"))
      (node (ref "U9") (pin "14") (pinfunction "ROSC_14") (pintype "input"))
    )
    (net (code "230") (name "Net-(U9-SENSE1)") (class "Default")
      (node (ref "R24") (pin "1") (pinfunction "1_1") (pintype "passive"))
      (node (ref "U9") (pin "25") (pinfunction "SENSE1_25") (pintype "input"))
    )
    (net (code "231") (name "Net-(U9-SENSE2)") (class "Default")
      (node (ref "R23") (pin "1") (pinfunction "1_1") (pintype "passive"))
      (node (ref "U9") (pin "32") (pinfunction "SENSE2_32") (pintype "input"))
    )
    (net (code "232") (name "Net-(U9-VCP)") (class "Default")
      (node (ref "C47") (pin "2") (pinfunction "2_2") (pintype "passive"))
      (node (ref "U9") (pin "9") (pinfunction "VCP_9") (pintype "bidirectional"))
    )
    (net (code "233") (name "Net-(U9-VREG)") (class "Default")
      (node (ref "C51") (pin "2") (pinfunction "2_2") (pintype "passive"))
      (node (ref "U9") (pin "10") (pinfunction "VREG_10") (pintype "input"))
    )
    (net (code "234") (name "Net-(U10-VOC)") (class "Default")
      (node (ref "R34") (pin "1") (pinfunction "1_1") (pintype "passive"))
      (node (ref "U10") (pin "12") (pinfunction "VOC_12") (pintype "bidirectional"))
    )
    (net (code "235") (name "Net-(X3B-S)") (class "Default")
      (node (ref "R27") (pin "1") (pinfunction "1_1") (pintype "passive"))
      (node (ref "R39") (pin "2") (pinfunction "2_2") (pintype "passive"))
      (node (ref "X3") (pin "2") (pinfunction "S_2") (pintype "passive"))
    )
    (net (code "236") (name "Net-(X4B-1)") (class "Default")
      (node (ref "CF6") (pin "3") (pinfunction "3_3") (pintype "passive"))
      (node (ref "X4") (pin "2") (pinfunction "1_2") (pintype "passive"))
    )
    (net (code "237") (name "Net-(X4C-1)") (class "Default")
      (node (ref "CF7") (pin "3") (pinfunction "3_3") (pintype "passive"))
      (node (ref "X4") (pin "3") (pinfunction "1_3") (pintype "passive"))
    )
    (net (code "238") (name "Net-(X4D-1)") (class "Default")
      (node (ref "CF8") (pin "3") (pinfunction "3_3") (pintype "passive"))
      (node (ref "X4") (pin "4") (pinfunction "1_4") (pintype "passive"))
    )
    (net (code "239") (name "Net-(X6B-1)") (class "Default")
      (node (ref "CF14") (pin "3") (pinfunction "3_3") (pintype "passive"))
      (node (ref "X6") (pin "2") (pinfunction "1_2") (pintype "passive"))
    )
    (net (code "240") (name "Net-(X6C-1)") (class "Default")
      (node (ref "CF15") (pin "3") (pinfunction "3_3") (pintype "passive"))
      (node (ref "X6") (pin "3") (pinfunction "1_3") (pintype "passive"))
    )
    (net (code "241") (name "Net-(X6D-1)") (class "Default")
      (node (ref "CF16") (pin "3") (pinfunction "3_3") (pintype "passive"))
      (node (ref "X6") (pin "4") (pinfunction "1_4") (pintype "passive"))
    )
    (net (code "242") (name "Net-(X7B-1)") (class "Default")
      (node (ref "CF18") (pin "3") (pinfunction "3_3") (pintype "passive"))
      (node (ref "X7") (pin "2") (pinfunction "1_2") (pintype "passive"))
    )
    (net (code "243") (name "Net-(X7C-1)") (class "Default")
      (node (ref "CF19") (pin "3") (pinfunction "3_3") (pintype "passive"))
      (node (ref "X7") (pin "3") (pinfunction "1_3") (pintype "passive"))
    )
    (net (code "244") (name "Net-(X7D-1)") (class "Default")
      (node (ref "CF20") (pin "3") (pinfunction "3_3") (pintype "passive"))
      (node (ref "X7") (pin "4") (pinfunction "1_4") (pintype "passive"))
    )
    (net (code "245") (name "Net-(X8B-1)") (class "Default")
      (node (ref "CF2") (pin "3") (pinfunction "3_3") (pintype "passive"))
      (node (ref "X8") (pin "2") (pinfunction "1_2") (pintype "passive"))
    )
    (net (code "246") (name "Net-(X8C-1)") (class "Default")
      (node (ref "CF3") (pin "3") (pinfunction "3_3") (pintype "passive"))
      (node (ref "X8") (pin "3") (pinfunction "1_3") (pintype "passive"))
    )
    (net (code "247") (name "Net-(X8D-1)") (class "Default")
      (node (ref "CF4") (pin "3") (pinfunction "3_3") (pintype "passive"))
      (node (ref "X8") (pin "4") (pinfunction "1_4") (pintype "passive"))
    )
    (net (code "248") (name "Net-(X14B-1)") (class "Default")
      (node (ref "CF10") (pin "3") (pinfunction "3_3") (pintype "passive"))
      (node (ref "X14") (pin "2") (pinfunction "1_2") (pintype "passive"))
      (node (ref "X15") (pin "2") (pinfunction "1_2") (pintype "passive"))
    )
    (net (code "249") (name "Net-(X14C-1)") (class "Default")
      (node (ref "CF11") (pin "3") (pinfunction "3_3") (pintype "passive"))
      (node (ref "X14") (pin "3") (pinfunction "1_3") (pintype "passive"))
      (node (ref "X15") (pin "3") (pinfunction "1_3") (pintype "passive"))
    )
    (net (code "250") (name "Net-(X14D-1)") (class "Default")
      (node (ref "CF12") (pin "3") (pinfunction "3_3") (pintype "passive"))
      (node (ref "X14") (pin "4") (pinfunction "1_4") (pintype "passive"))
      (node (ref "X15") (pin "4") (pinfunction "1_4") (pintype "passive"))
    )
    (net (code "251") (name "Net-(X27B-S)") (class "Default")
      (node (ref "R31") (pin "1") (pinfunction "1_1") (pintype "passive"))
      (node (ref "R32") (pin "2") (pinfunction "2_2") (pintype "passive"))
      (node (ref "X27") (pin "2") (pinfunction "S_2") (pintype "passive"))
    )
    (net (code "252") (name "Net-(X28B-S)") (class "Default")
      (node (ref "R36") (pin "1") (pinfunction "1_1") (pintype "passive"))
      (node (ref "R37") (pin "2") (pinfunction "2_2") (pintype "passive"))
      (node (ref "X28") (pin "2") (pinfunction "S_2") (pintype "passive"))
    )
    (net (code "253") (name "Net-(X29B-S)") (class "Default")
      (node (ref "R28") (pin "2") (pinfunction "2_2") (pintype "passive"))
      (node (ref "R38") (pin "1") (pinfunction "1_1") (pintype "passive"))
      (node (ref "X29") (pin "2") (pinfunction "S_2") (pintype "passive"))
    )
    (net (code "254") (name "VCC") (class "Default")
      (node (ref "C20") (pin "1") (pinfunction "1_1") (pintype "passive"))
      (node (ref "C21") (pin "2") (pinfunction "2_2") (pintype "passive"))
      (node (ref "C25") (pin "1") (pinfunction "1_1") (pintype "passive"))
      (node (ref "C30") (pin "1") (pinfunction "1_1") (pintype "passive"))
      (node (ref "C52") (pin "1") (pinfunction "1_1") (pintype "passive"))
      (node (ref "C53") (pin "1") (pinfunction "1_1") (pintype "passive"))
      (node (ref "C55") (pin "1") (pinfunction "1_1") (pintype "passive"))
      (node (ref "C7") (pin "1") (pinfunction "1_1") (pintype "passive"))
      (node (ref "C8") (pin "1") (pinfunction "1_1") (pintype "passive"))
      (node (ref "C9") (pin "1") (pinfunction "1_1") (pintype "passive"))
      (node (ref "D5") (pin "C") (pinfunction "C_C") (pintype "passive"))
      (node (ref "L2") (pin "1") (pinfunction "1_1") (pintype "passive"))
      (node (ref "L3") (pin "P$2") (pinfunction "2_P$2") (pintype "passive"))
      (node (ref "R13") (pin "2") (pinfunction "2_2") (pintype "passive"))
      (node (ref "R27") (pin "2") (pinfunction "2_2") (pintype "passive"))
      (node (ref "R29") (pin "2") (pinfunction "2_2") (pintype "passive"))
      (node (ref "R30") (pin "1") (pinfunction "1_1") (pintype "passive"))
      (node (ref "R31") (pin "2") (pinfunction "2_2") (pintype "passive"))
      (node (ref "R35") (pin "1") (pinfunction "1_1") (pintype "passive"))
      (node (ref "R36") (pin "2") (pinfunction "2_2") (pintype "passive"))
      (node (ref "R38") (pin "2") (pinfunction "2_2") (pintype "passive"))
      (node (ref "R44") (pin "2") (pinfunction "2_2") (pintype "passive"))
      (node (ref "R45") (pin "2") (pinfunction "2_2") (pintype "passive"))
      (node (ref "R46") (pin "2") (pinfunction "2_2") (pintype "passive"))
      (node (ref "R59") (pin "1") (pinfunction "1_1") (pintype "passive"))
      (node (ref "R60") (pin "1") (pinfunction "1_1") (pintype "passive"))
      (node (ref "R61") (pin "1") (pinfunction "1_1") (pintype "passive"))
      (node (ref "R62") (pin "1") (pinfunction "1_1") (pintype "passive"))
      (node (ref "R63") (pin "1") (pinfunction "1_1") (pintype "passive"))
      (node (ref "R65") (pin "2") (pinfunction "2_2") (pintype "passive"))
      (node (ref "R66") (pin "2") (pinfunction "2_2") (pintype "passive"))
      (node (ref "R67") (pin "2") (pinfunction "2_2") (pintype "passive"))
      (node (ref "R68") (pin "2") (pinfunction "2_2") (pintype "passive"))
      (node (ref "U10") (pin "10") (pinfunction "VDD2B_10") (pintype "bidirectional"))
      (node (ref "U10") (pin "16") (pinfunction "VDD2A_16") (pintype "bidirectional"))
      (node (ref "U2") (pin "10") (pinfunction "VCC_10") (pintype "power_in"))
      (node (ref "U2") (pin "31") (pinfunction "VCC1_31") (pintype "power_in"))
      (node (ref "U2") (pin "61") (pinfunction "VCC2_61") (pintype "power_in"))
      (node (ref "U2") (pin "80") (pinfunction "VCC3_80") (pintype "power_in"))
      (node (ref "U4") (pin "P06") (pinfunction "VDD_P06") (pintype "bidirectional"))
      (node (ref "X1") (pin "2") (pinfunction "S_2") (pintype "passive"))
      (node (ref "X10") (pin "1") (pinfunction "S_1") (pintype "passive"))
      (node (ref "X12") (pin "1") (pinfunction "1_1") (pintype "passive"))
      (node (ref "X13") (pin "1") (pinfunction "1_1") (pintype "passive"))
      (node (ref "X13") (pin "2") (pinfunction "2_2") (pintype "passive"))
      (node (ref "X18") (pin "2") (pinfunction "2_2") (pintype "passive"))
      (node (ref "X20") (pin "1") (pinfunction "1_1") (pintype "passive"))
      (node (ref "X21") (pin "3") (pinfunction "S_3") (pintype "passive"))
      (node (ref "X22") (pin "3") (pinfunction "S_3") (pintype "passive"))
      (node (ref "X23") (pin "3") (pinfunction "S_3") (pintype "passive"))
      (node (ref "X24") (pin "3") (pinfunction "S_3") (pintype "passive"))
      (node (ref "X25") (pin "3") (pinfunction "S_3") (pintype "passive"))
      (node (ref "X26") (pin "3") (pinfunction "S_3") (pintype "passive"))
      (node (ref "X31") (pin "1") (pinfunction "1_1") (pintype "passive"))
      (node (ref "X32") (pin "1") (pinfunction "1_1") (pintype "passive"))
      (node (ref "X34") (pin "1") (pinfunction "1_1") (pintype "passive"))
      (node (ref "X39") (pin "1") (pinfunction "1_1") (pintype "passive"))
      (node (ref "X40") (pin "1") (pinfunction "1_1") (pintype "passive"))
      (node (ref "X5") (pin "2") (pinfunction "S_2") (pintype "passive"))
    )
    (net (code "255") (name "unconnected-(RN5-Pad1)") (class "Default")
      (node (ref "RN5") (pin "1") (pinfunction "1_1") (pintype "passive"))
    )
    (net (code "256") (name "unconnected-(U3-NC-Pad2)") (class "Default")
      (node (ref "U3") (pin "2") (pinfunction "NC_2") (pintype "bidirectional"))
    )
    (net (code "257") (name "unconnected-(U3-NC1-Pad3)") (class "Default")
      (node (ref "U3") (pin "3") (pinfunction "NC1_3") (pintype "bidirectional"))
    )
    (net (code "258") (name "unconnected-(U5-NC1-Pad2)") (class "Default")
      (node (ref "U5") (pin "2") (pinfunction "NC1_2") (pintype "output"))
    )
    (net (code "259") (name "unconnected-(U5-NC2-Pad4)") (class "Default")
      (node (ref "U5") (pin "4") (pinfunction "NC2_4") (pintype "output"))
    )
    (net (code "260") (name "unconnected-(U5-NC3-Pad21)") (class "Default")
      (node (ref "U5") (pin "21") (pinfunction "NC3_21") (pintype "output"))
    )
    (net (code "261") (name "unconnected-(U5-NC4-Pad23)") (class "Default")
      (node (ref "U5") (pin "23") (pinfunction "NC4_23") (pintype "output"))
    )
    (net (code "262") (name "unconnected-(U5-NC5-Pad26)") (class "Default")
      (node (ref "U5") (pin "26") (pinfunction "NC5_26") (pintype "output"))
    )
    (net (code "263") (name "unconnected-(U5-NC6-Pad28)") (class "Default")
      (node (ref "U5") (pin "28") (pinfunction "NC6_28") (pintype "output"))
    )
    (net (code "264") (name "unconnected-(U5-NC7-Pad29)") (class "Default")
      (node (ref "U5") (pin "29") (pinfunction "NC7_29") (pintype "output"))
    )
    (net (code "265") (name "unconnected-(U5-NC8-Pad31)") (class "Default")
      (node (ref "U5") (pin "31") (pinfunction "NC8_31") (pintype "output"))
    )
    (net (code "266") (name "unconnected-(U6-NC1-Pad2)") (class "Default")
      (node (ref "U6") (pin "2") (pinfunction "NC1_2") (pintype "output"))
    )
    (net (code "267") (name "unconnected-(U6-NC2-Pad4)") (class "Default")
      (node (ref "U6") (pin "4") (pinfunction "NC2_4") (pintype "output"))
    )
    (net (code "268") (name "unconnected-(U6-NC3-Pad21)") (class "Default")
      (node (ref "U6") (pin "21") (pinfunction "NC3_21") (pintype "output"))
    )
    (net (code "269") (name "unconnected-(U6-NC4-Pad23)") (class "Default")
      (node (ref "U6") (pin "23") (pinfunction "NC4_23") (pintype "output"))
    )
    (net (code "270") (name "unconnected-(U6-NC5-Pad26)") (class "Default")
      (node (ref "U6") (pin "26") (pinfunction "NC5_26") (pintype "output"))
    )
    (net (code "271") (name "unconnected-(U6-NC6-Pad28)") (class "Default")
      (node (ref "U6") (pin "28") (pinfunction "NC6_28") (pintype "output"))
    )
    (net (code "272") (name "unconnected-(U6-NC7-Pad29)") (class "Default")
      (node (ref "U6") (pin "29") (pinfunction "NC7_29") (pintype "output"))
    )
    (net (code "273") (name "unconnected-(U6-NC8-Pad31)") (class "Default")
      (node (ref "U6") (pin "31") (pinfunction "NC8_31") (pintype "output"))
    )
    (net (code "274") (name "unconnected-(U7-NC1-Pad2)") (class "Default")
      (node (ref "U7") (pin "2") (pinfunction "NC1_2") (pintype "output"))
    )
    (net (code "275") (name "unconnected-(U7-NC2-Pad4)") (class "Default")
      (node (ref "U7") (pin "4") (pinfunction "NC2_4") (pintype "output"))
    )
    (net (code "276") (name "unconnected-(U7-NC3-Pad21)") (class "Default")
      (node (ref "U7") (pin "21") (pinfunction "NC3_21") (pintype "output"))
    )
    (net (code "277") (name "unconnected-(U7-NC4-Pad23)") (class "Default")
      (node (ref "U7") (pin "23") (pinfunction "NC4_23") (pintype "output"))
    )
    (net (code "278") (name "unconnected-(U7-NC5-Pad26)") (class "Default")
      (node (ref "U7") (pin "26") (pinfunction "NC5_26") (pintype "output"))
    )
    (net (code "279") (name "unconnected-(U7-NC6-Pad28)") (class "Default")
      (node (ref "U7") (pin "28") (pinfunction "NC6_28") (pintype "output"))
    )
    (net (code "280") (name "unconnected-(U7-NC7-Pad29)") (class "Default")
      (node (ref "U7") (pin "29") (pinfunction "NC7_29") (pintype "output"))
    )
    (net (code "281") (name "unconnected-(U7-NC8-Pad31)") (class "Default")
      (node (ref "U7") (pin "31") (pinfunction "NC8_31") (pintype "output"))
    )
    (net (code "282") (name "unconnected-(U8-NC1-Pad2)") (class "Default")
      (node (ref "U8") (pin "2") (pinfunction "NC1_2") (pintype "output"))
    )
    (net (code "283") (name "unconnected-(U8-NC2-Pad4)") (class "Default")
      (node (ref "U8") (pin "4") (pinfunction "NC2_4") (pintype "output"))
    )
    (net (code "284") (name "unconnected-(U8-NC3-Pad21)") (class "Default")
      (node (ref "U8") (pin "21") (pinfunction "NC3_21") (pintype "output"))
    )
    (net (code "285") (name "unconnected-(U8-NC4-Pad23)") (class "Default")
      (node (ref "U8") (pin "23") (pinfunction "NC4_23") (pintype "output"))
    )
    (net (code "286") (name "unconnected-(U8-NC5-Pad26)") (class "Default")
      (node (ref "U8") (pin "26") (pinfunction "NC5_26") (pintype "output"))
    )
    (net (code "287") (name "unconnected-(U8-NC6-Pad28)") (class "Default")
      (node (ref "U8") (pin "28") (pinfunction "NC6_28") (pintype "output"))
    )
    (net (code "288") (name "unconnected-(U8-NC7-Pad29)") (class "Default")
      (node (ref "U8") (pin "29") (pinfunction "NC7_29") (pintype "output"))
    )
    (net (code "289") (name "unconnected-(U8-NC8-Pad31)") (class "Default")
      (node (ref "U8") (pin "31") (pinfunction "NC8_31") (pintype "output"))
    )
    (net (code "290") (name "unconnected-(U9-NC1-Pad2)") (class "Default")
      (node (ref "U9") (pin "2") (pinfunction "NC1_2") (pintype "output"))
    )
    (net (code "291") (name "unconnected-(U9-NC2-Pad4)") (class "Default")
      (node (ref "U9") (pin "4") (pinfunction "NC2_4") (pintype "output"))
    )
    (net (code "292") (name "unconnected-(U9-NC3-Pad21)") (class "Default")
      (node (ref "U9") (pin "21") (pinfunction "NC3_21") (pintype "output"))
    )
    (net (code "293") (name "unconnected-(U9-NC4-Pad23)") (class "Default")
      (node (ref "U9") (pin "23") (pinfunction "NC4_23") (pintype "output"))
    )
    (net (code "294") (name "unconnected-(U9-NC5-Pad26)") (class "Default")
      (node (ref "U9") (pin "26") (pinfunction "NC5_26") (pintype "output"))
    )
    (net (code "295") (name "unconnected-(U9-NC6-Pad28)") (class "Default")
      (node (ref "U9") (pin "28") (pinfunction "NC6_28") (pintype "output"))
    )
    (net (code "296") (name "unconnected-(U9-NC7-Pad29)") (class "Default")
      (node (ref "U9") (pin "29") (pinfunction "NC7_29") (pintype "output"))
    )
    (net (code "297") (name "unconnected-(U9-NC8-Pad31)") (class "Default")
      (node (ref "U9") (pin "31") (pinfunction "NC8_31") (pintype "output"))
    )
    (net (code "298") (name "unconnected-(U10-VOB-Pad13)") (class "Default")
      (node (ref "U10") (pin "13") (pinfunction "VOB_13") (pintype "bidirectional"))
    )
    (net (code "299") (name "unconnected-(X12-Pad8)") (class "Default")
      (node (ref "X12") (pin "8") (pinfunction "8_8") (pintype "passive"))
    )
  )
)
